# 612_jetracer_esp32s3_030100.net
KiCad netlist of a schematic drawn in EAGLE
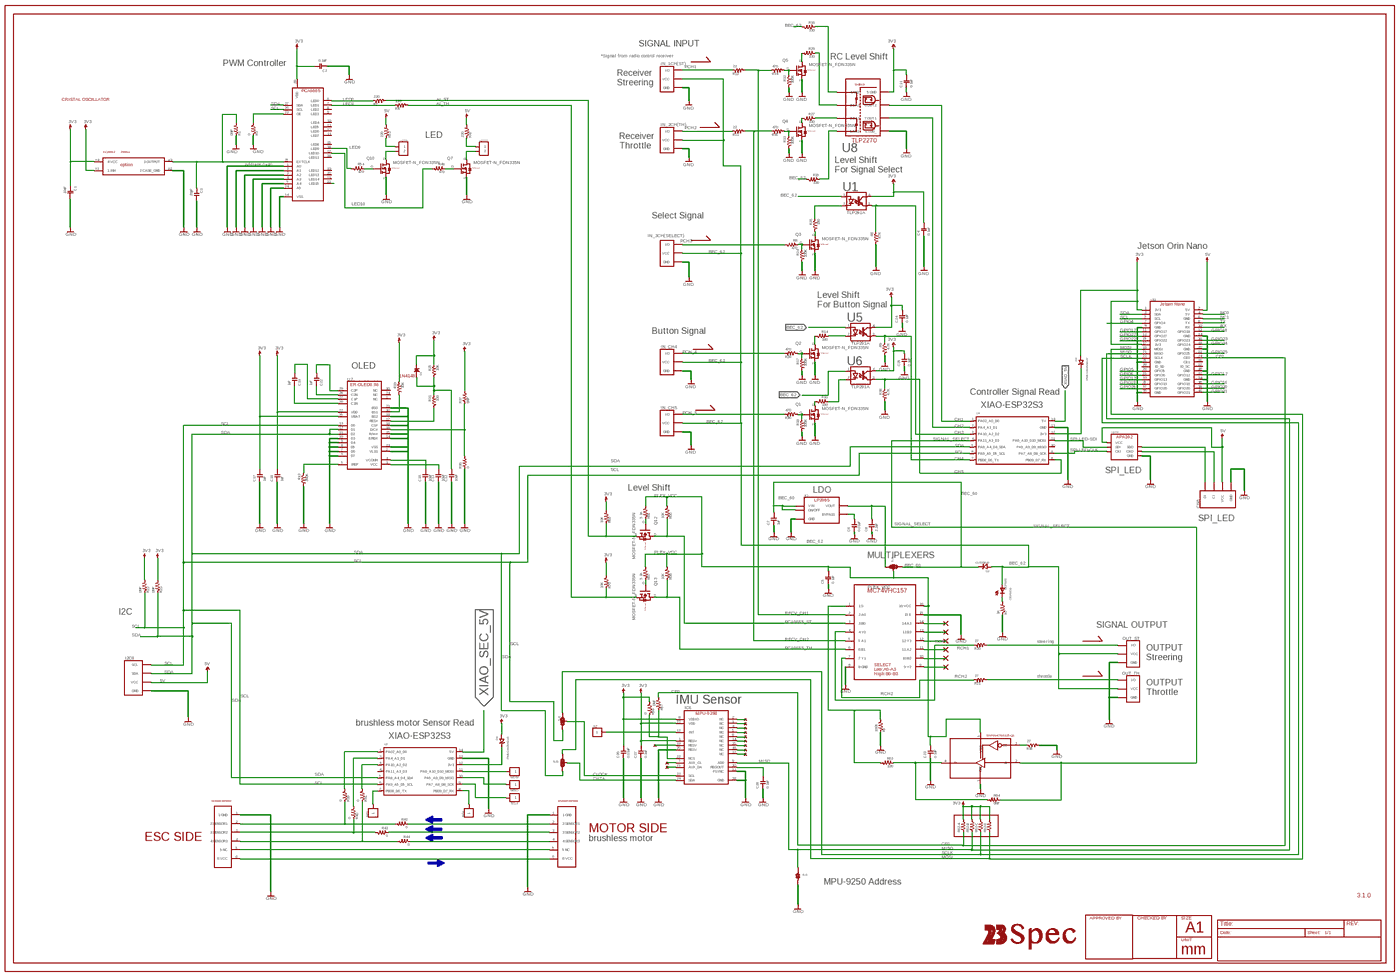
[diagram p0: schematic, sheet 1, overview]
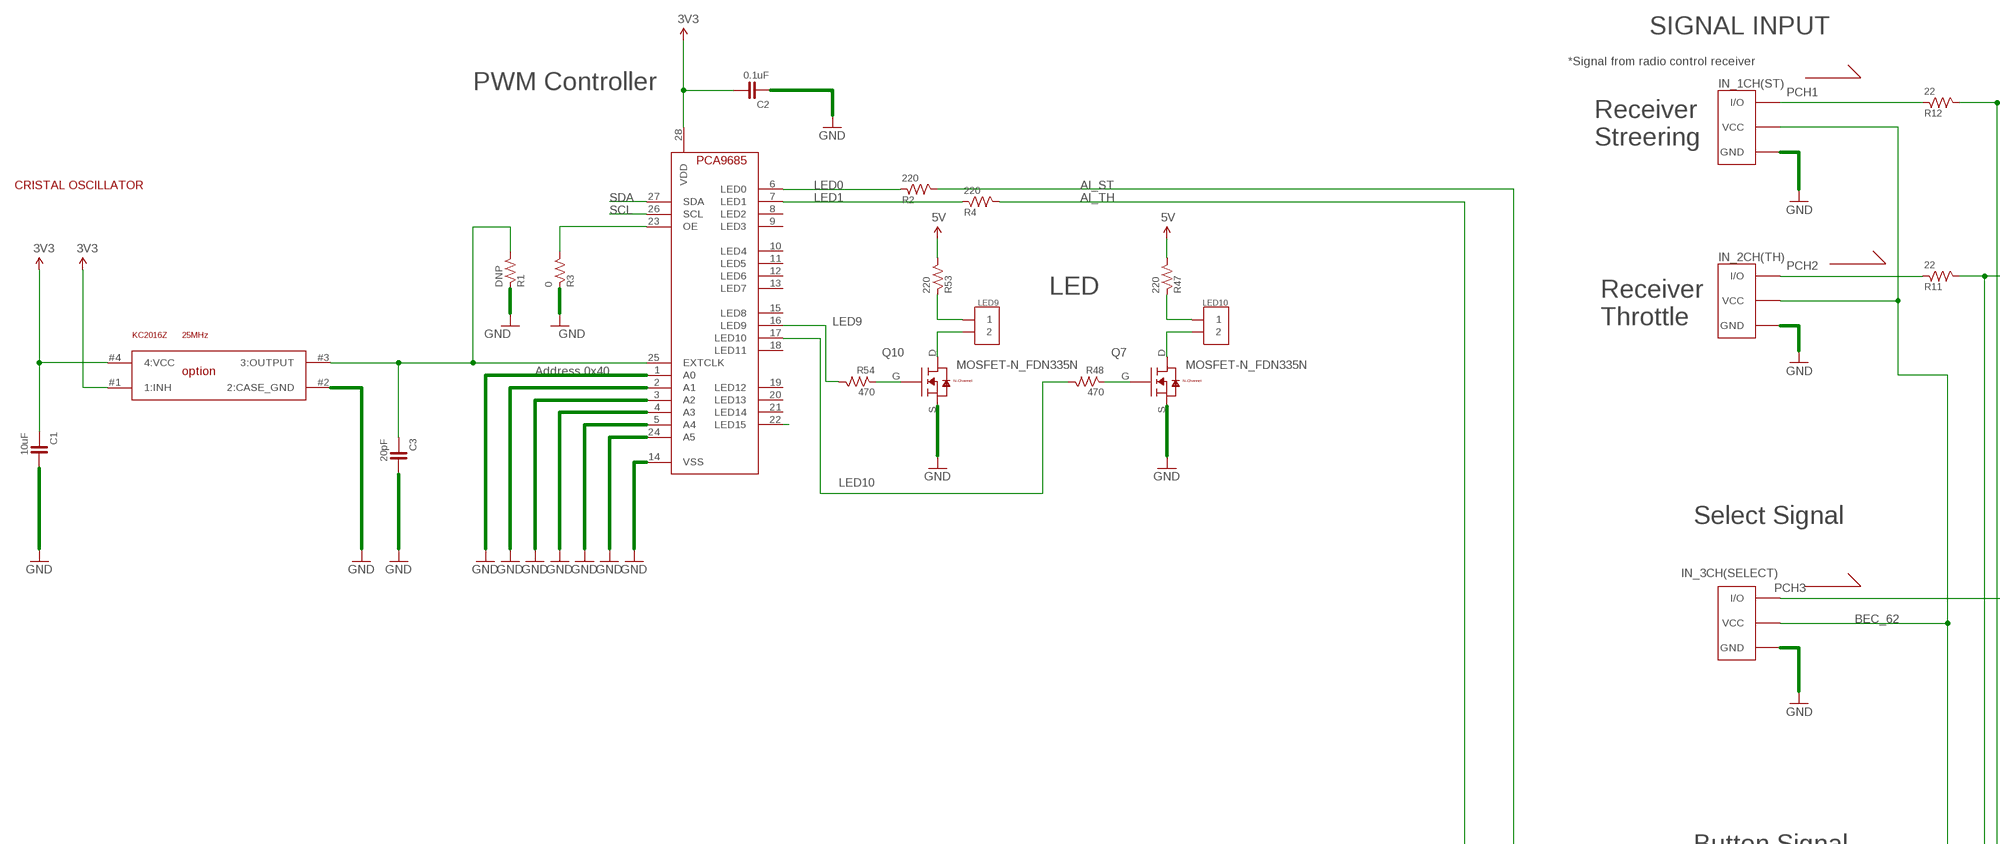
[diagram p1: schematic, sheet 1, part 1 of 4]
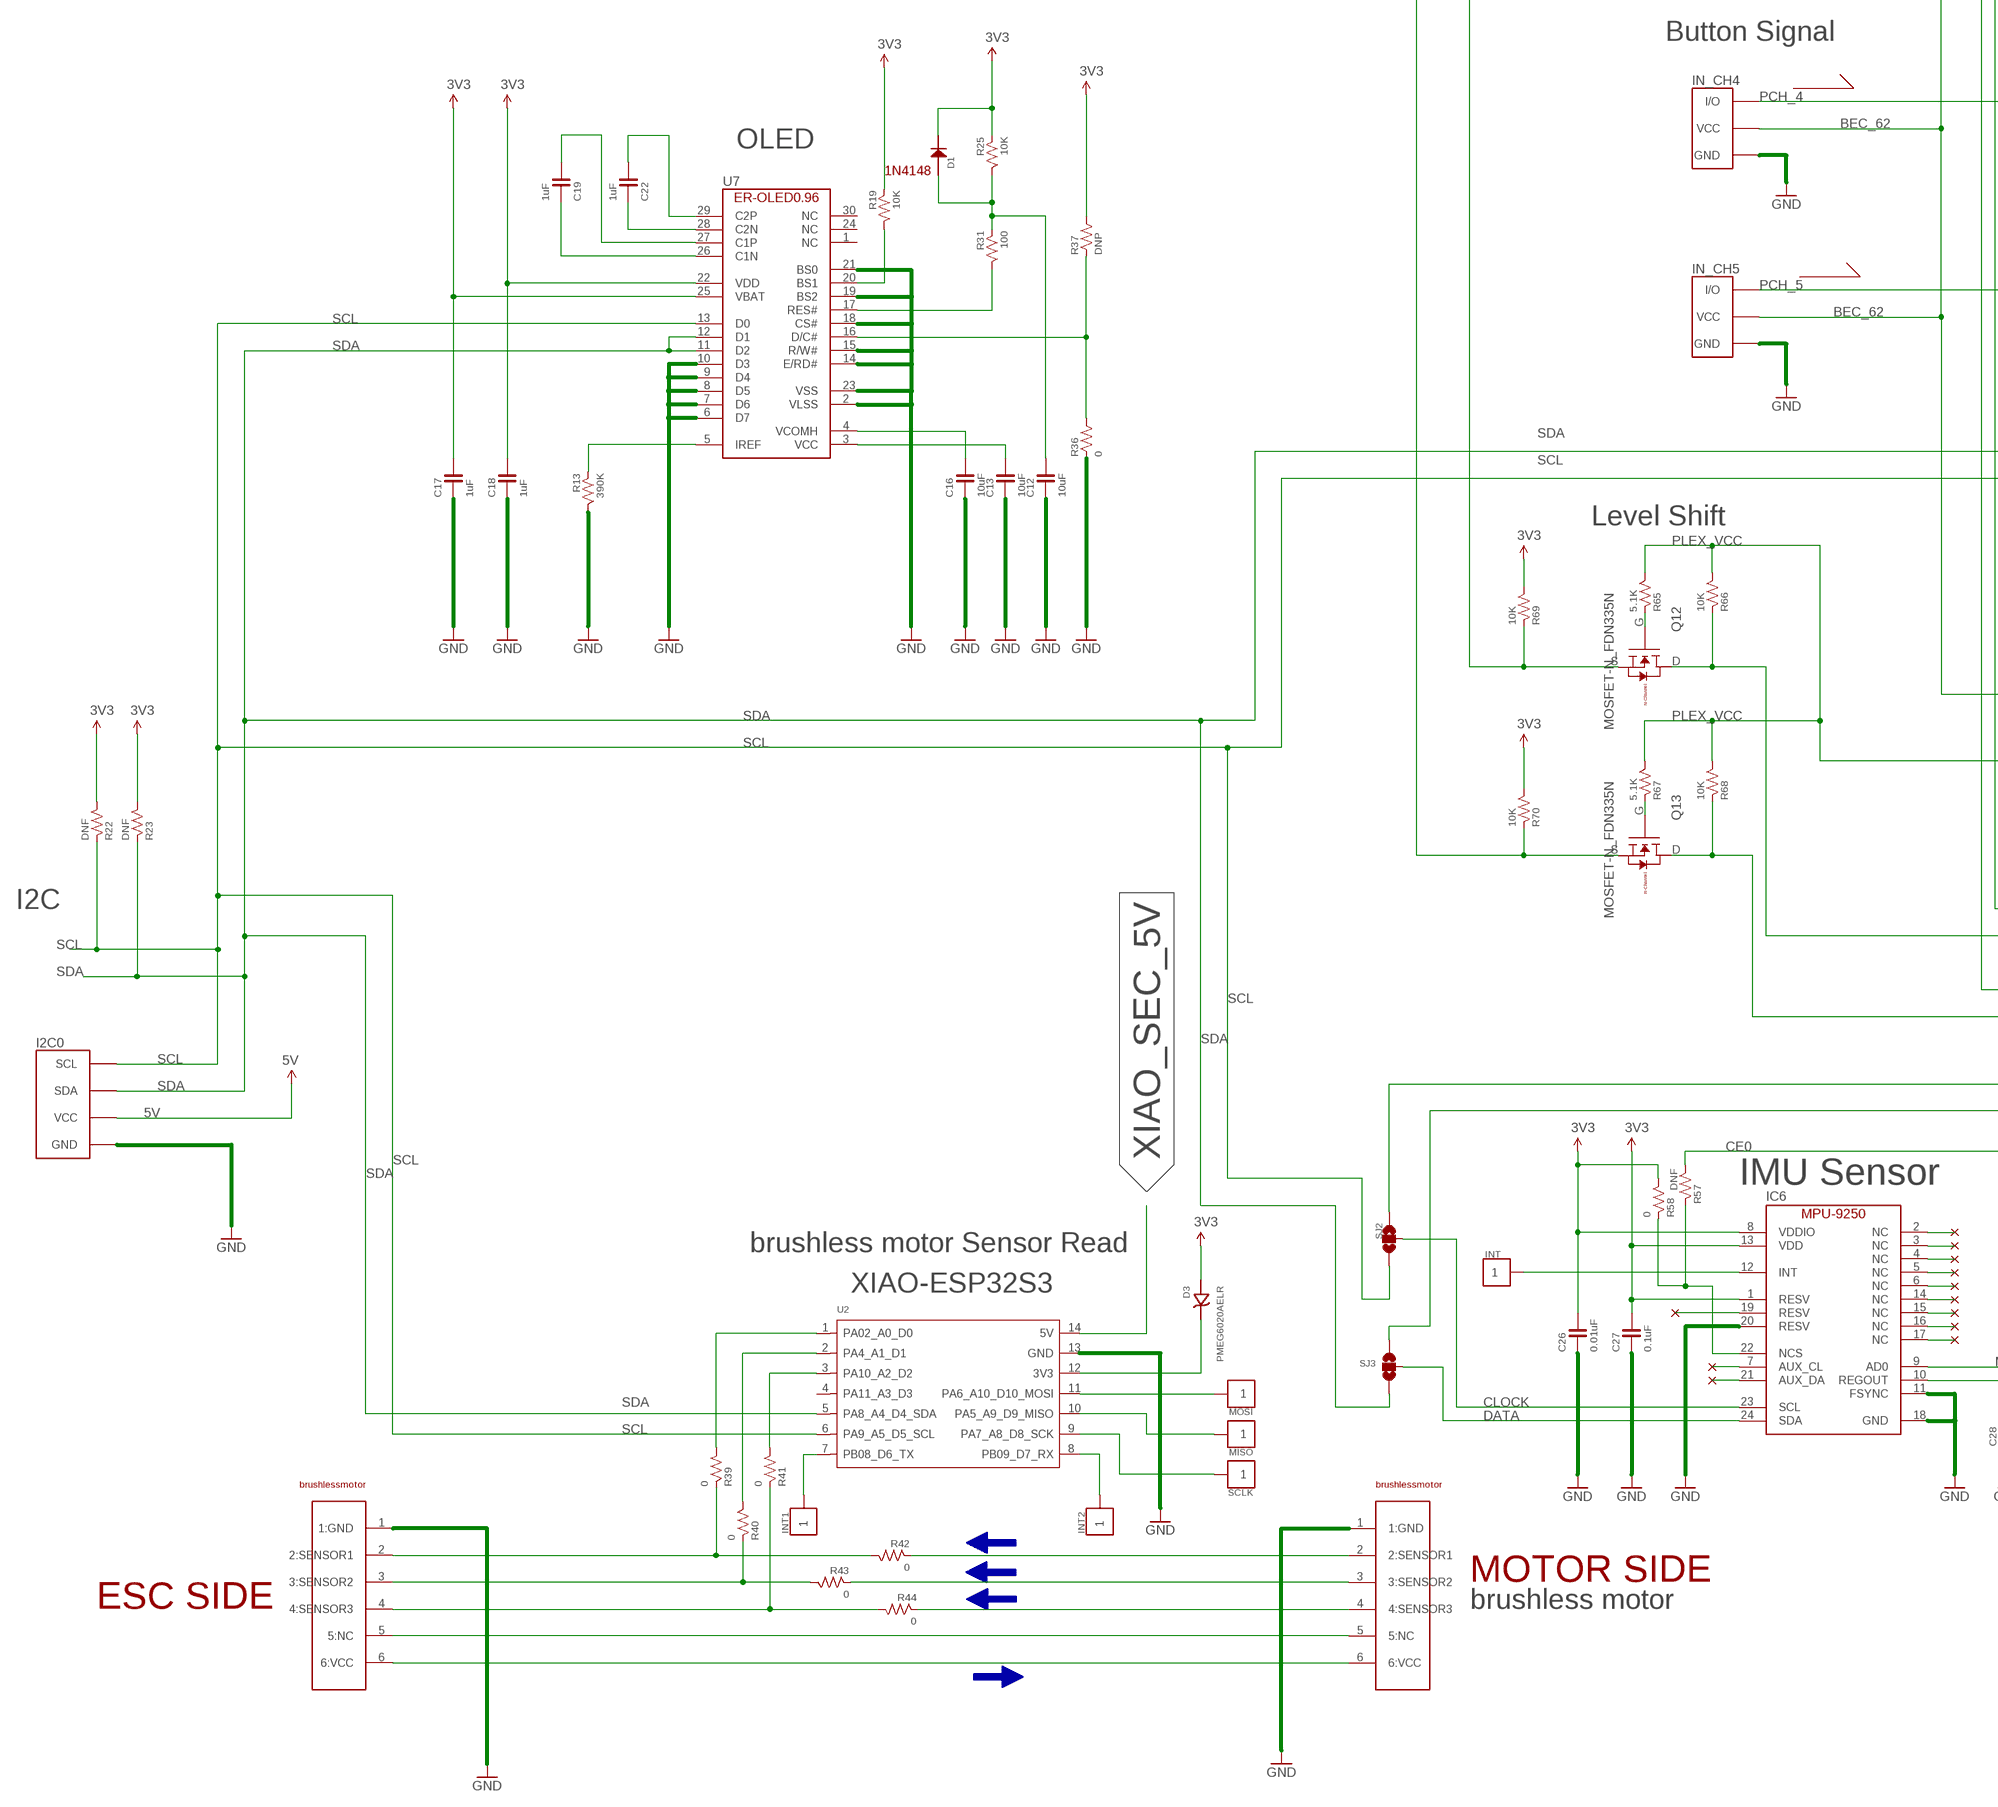
[diagram p2: schematic, sheet 1, part 2 of 4]
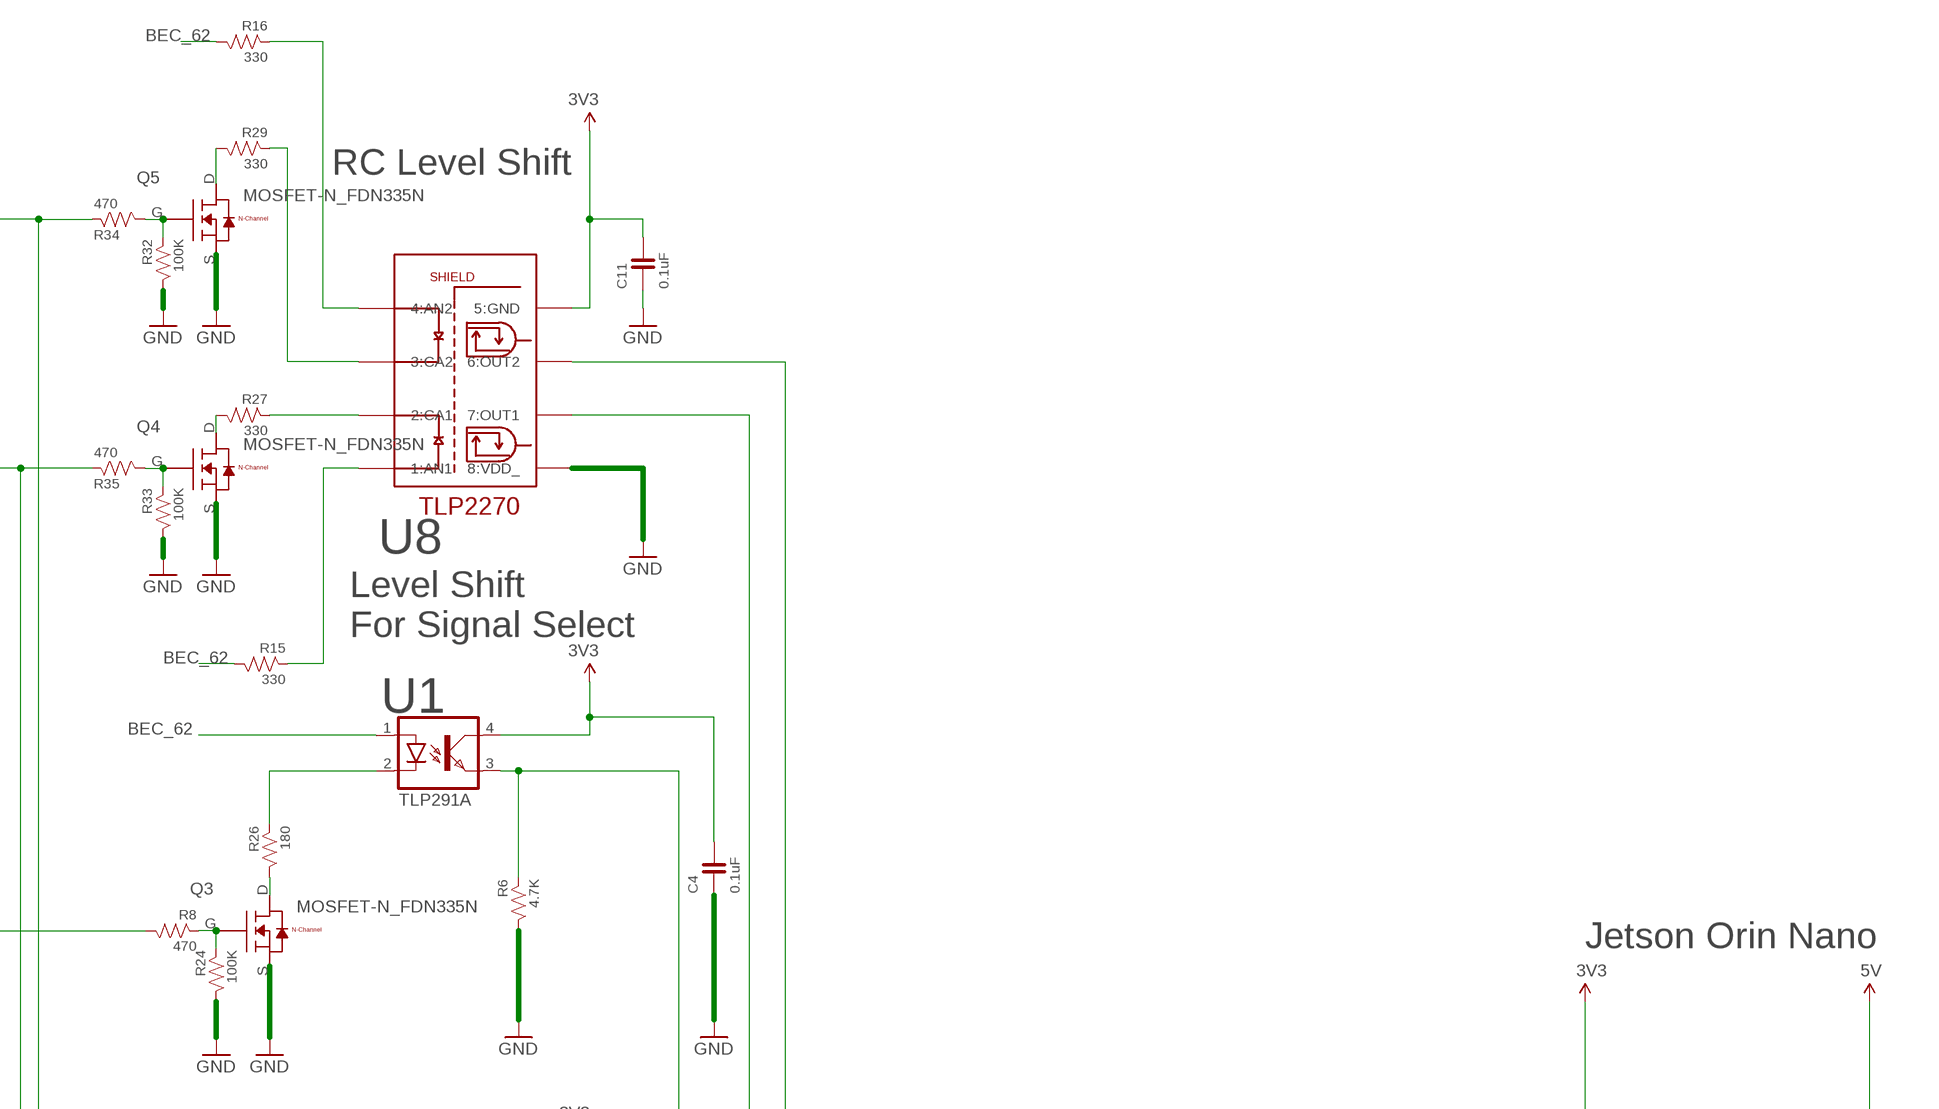
[diagram p3: schematic, sheet 1, part 3 of 4]
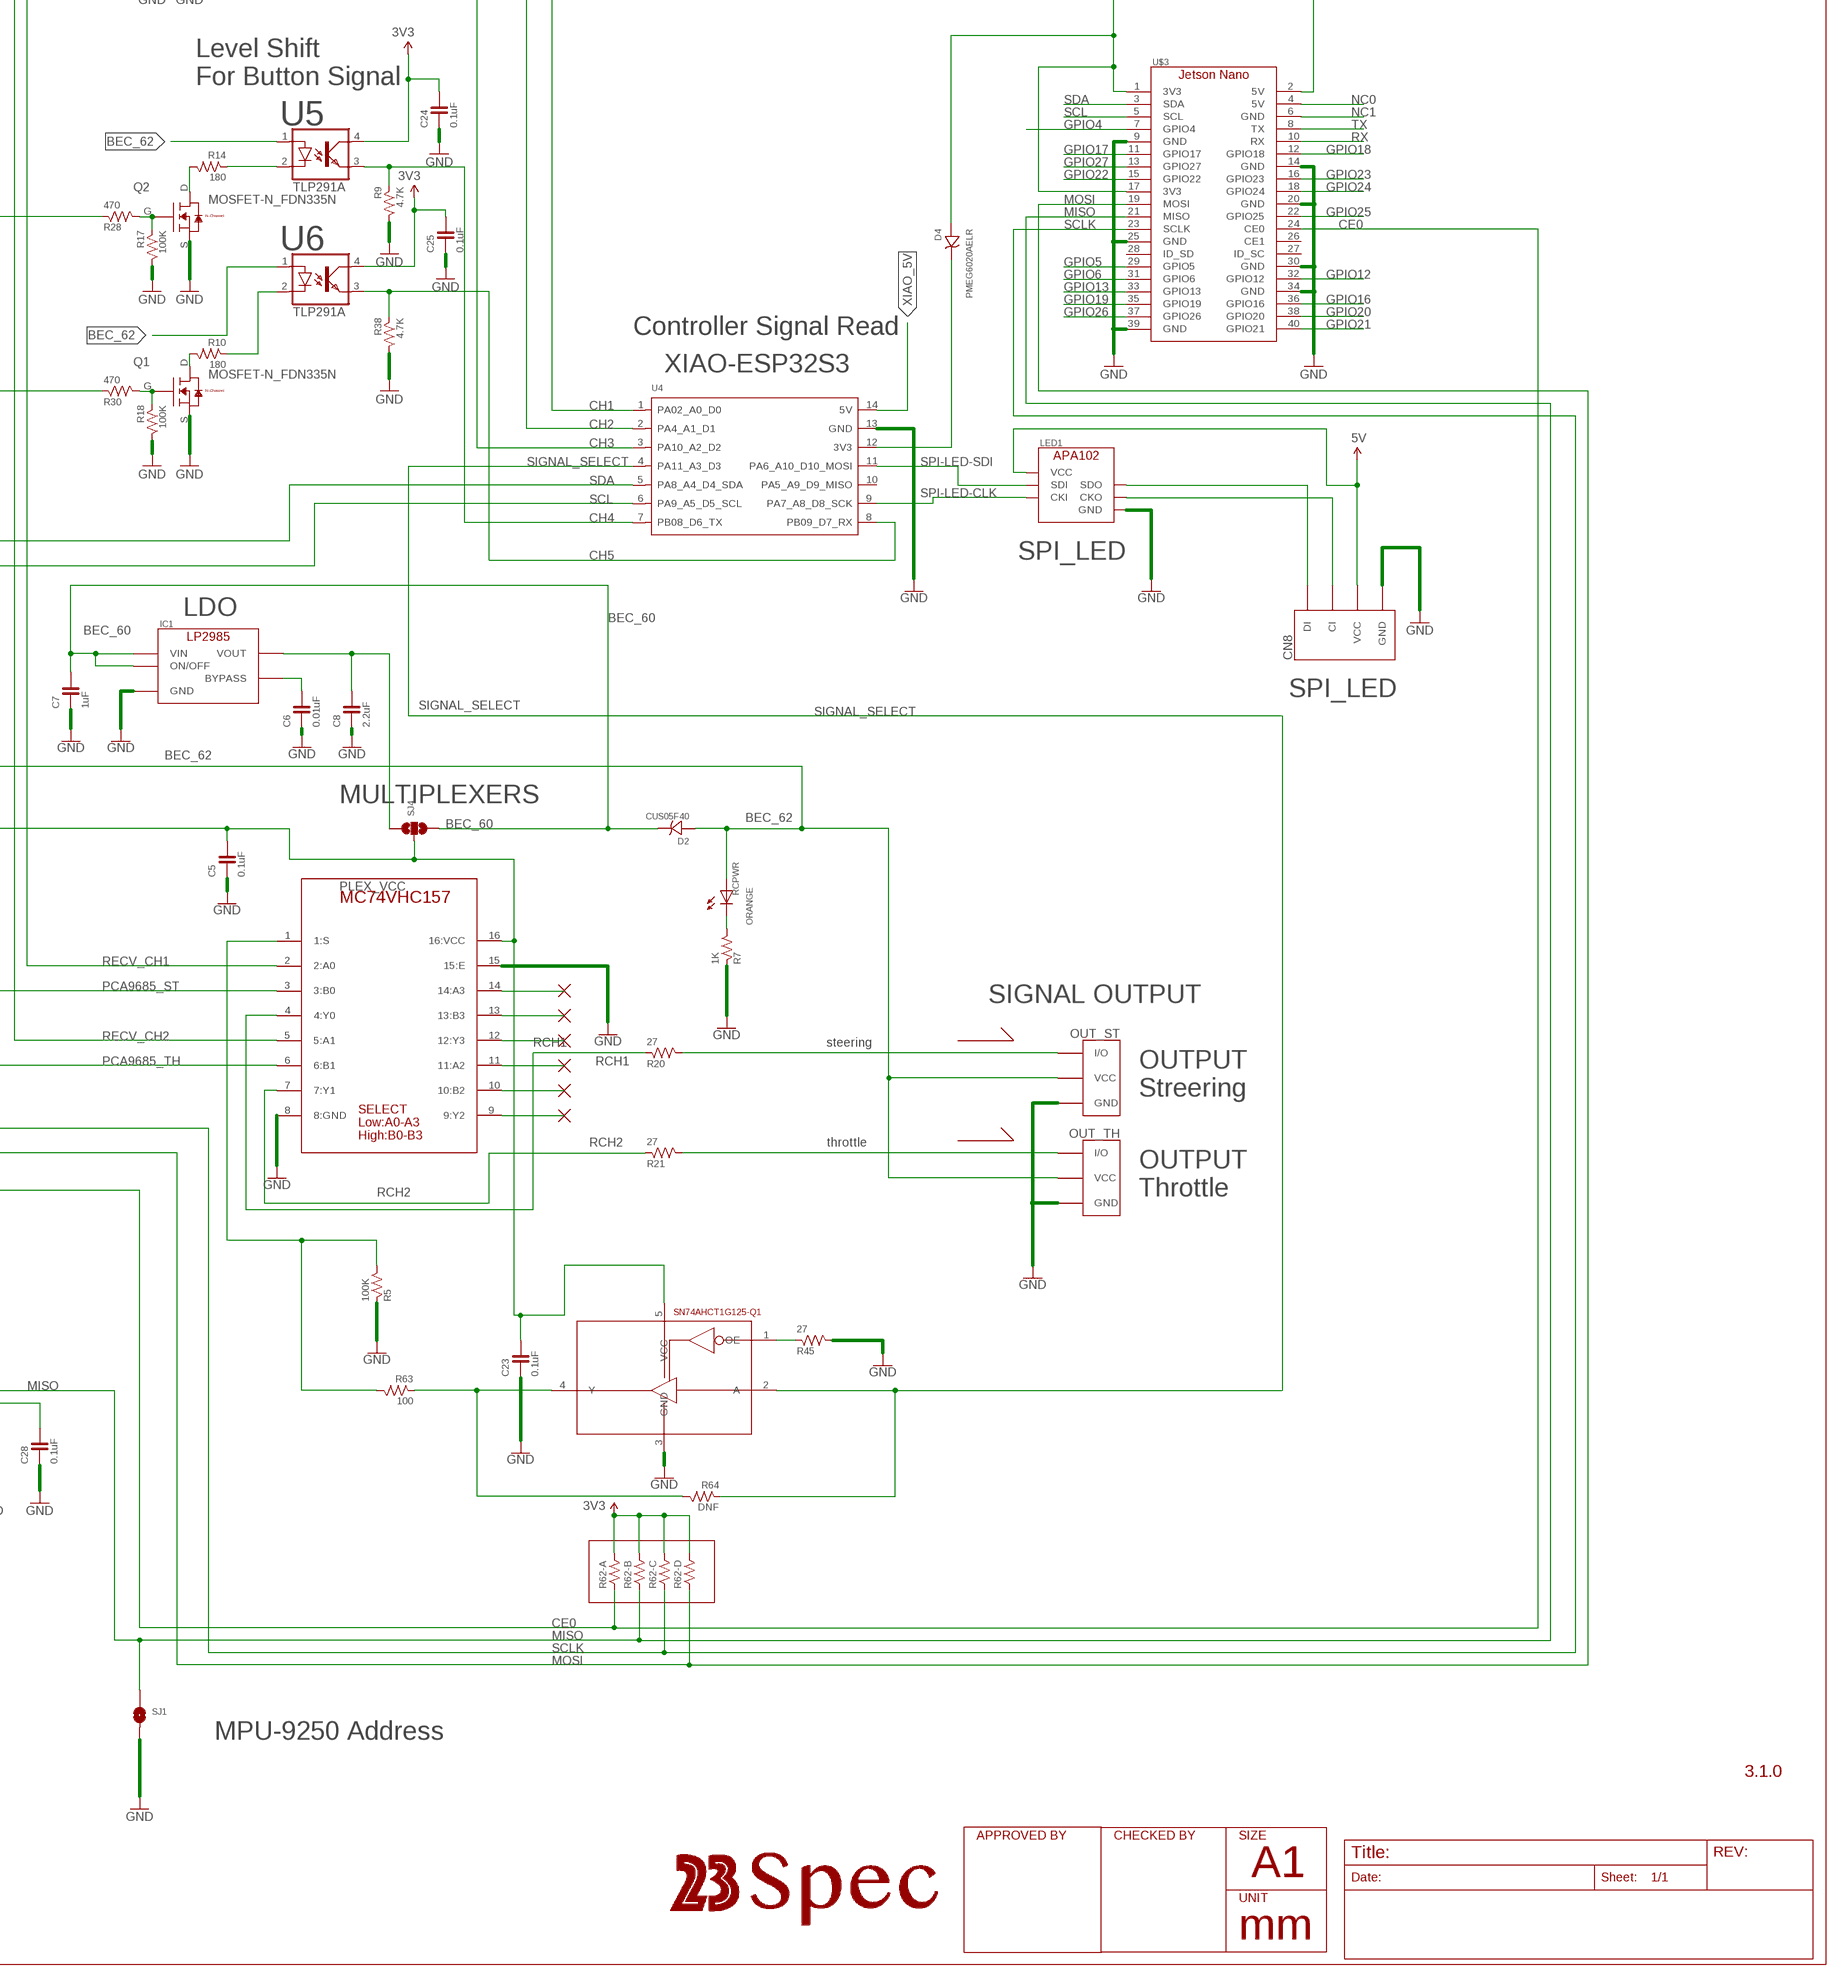
[diagram p4: schematic, sheet 1, part 4 of 4]

(export (version "E")
  (design (tool "Eeschema 10.0.6"))
  (components
    (comp (ref "C1")
      (value "10uF")
      (footprint "eagle-import:0603")
      (libsource (lib "eagle-import") (part "CAPACITOR-0603"))
    )
    (comp (ref "C2")
      (value "0.1uF")
      (footprint "eagle-import:0603")
      (libsource (lib "eagle-import") (part "CAPACITOR-0603"))
    )
    (comp (ref "C3")
      (value "20pF")
      (footprint "eagle-import:0603")
      (libsource (lib "eagle-import") (part "CAPACITOR-0603"))
    )
    (comp (ref "C4")
      (value "0.1uF")
      (footprint "eagle-import:0603")
      (libsource (lib "eagle-import") (part "CAPACITOR-0603"))
    )
    (comp (ref "C5")
      (value "0.1uF")
      (footprint "eagle-import:0603")
      (libsource (lib "eagle-import") (part "CAPACITOR-0603"))
    )
    (comp (ref "C6")
      (value "0.01uF")
      (footprint "eagle-import:0603")
      (libsource (lib "eagle-import") (part "CAPACITOR-0603"))
    )
    (comp (ref "C7")
      (value "1uF")
      (footprint "eagle-import:0603")
      (libsource (lib "eagle-import") (part "CAPACITOR-0603"))
    )
    (comp (ref "C8")
      (value "2.2uF")
      (footprint "eagle-import:0603")
      (libsource (lib "eagle-import") (part "CAPACITOR-0603"))
    )
    (comp (ref "C11")
      (value "0.1uF")
      (footprint "eagle-import:0603")
      (libsource (lib "eagle-import") (part "CAPACITOR-0603"))
    )
    (comp (ref "C12")
      (value "10uF")
      (footprint "eagle-import:0603")
      (libsource (lib "eagle-import") (part "CAPACITOR-0603"))
    )
    (comp (ref "C13")
      (value "10uF")
      (footprint "eagle-import:0603")
      (libsource (lib "eagle-import") (part "CAPACITOR-0603"))
    )
    (comp (ref "C16")
      (value "10uF")
      (footprint "eagle-import:0603")
      (libsource (lib "eagle-import") (part "CAPACITOR-0603"))
    )
    (comp (ref "C17")
      (value "1uF")
      (footprint "eagle-import:0603")
      (libsource (lib "eagle-import") (part "CAPACITOR-0603"))
    )
    (comp (ref "C18")
      (value "1uF")
      (footprint "eagle-import:0603")
      (libsource (lib "eagle-import") (part "CAPACITOR-0603"))
    )
    (comp (ref "C19")
      (value "1uF")
      (footprint "eagle-import:0603")
      (libsource (lib "eagle-import") (part "CAPACITOR-0603"))
    )
    (comp (ref "C22")
      (value "1uF")
      (footprint "eagle-import:0603")
      (libsource (lib "eagle-import") (part "CAPACITOR-0603"))
    )
    (comp (ref "C23")
      (value "0.1uF")
      (footprint "eagle-import:0603")
      (libsource (lib "eagle-import") (part "CAPACITOR-0603"))
    )
    (comp (ref "C24")
      (value "0.1uF")
      (footprint "eagle-import:0603")
      (libsource (lib "eagle-import") (part "CAPACITOR-0603"))
    )
    (comp (ref "C25")
      (value "0.1uF")
      (footprint "eagle-import:0603")
      (libsource (lib "eagle-import") (part "CAPACITOR-0603"))
    )
    (comp (ref "C26")
      (value "0.01uF")
      (footprint "eagle-import:0603")
      (libsource (lib "eagle-import") (part "CAPACITOR-0603"))
    )
    (comp (ref "C27")
      (value "0.1uF")
      (footprint "eagle-import:0603")
      (libsource (lib "eagle-import") (part "CAPACITOR-0603"))
    )
    (comp (ref "C28")
      (value "0.1uF")
      (footprint "eagle-import:0603")
      (libsource (lib "eagle-import") (part "CAPACITOR-0603"))
    )
    (comp (ref "CN8")
      (value "FABO-SPI-LED-B04B")
      (footprint "eagle-import:SPI-B04B-PASK-1")
      (libsource (lib "eagle-import") (part "FABO-SPI-LED-B04B"))
    )
    (comp (ref "D1")
      (value "1N4148")
      (footprint "eagle-import:1N4148W")
      (libsource (lib "eagle-import") (part "1N4148"))
    )
    (comp (ref "D2")
      (value "CUS05F40")
      (footprint "eagle-import:CUS05F40")
      (libsource (lib "eagle-import") (part "CUS05F40"))
    )
    (comp (ref "D3")
      (value "PMEG6020AELR")
      (footprint "eagle-import:SOD123W")
      (libsource (lib "eagle-import") (part "PMEG6020AELR"))
    )
    (comp (ref "D4")
      (value "PMEG6020AELR")
      (footprint "eagle-import:SOD123W")
      (libsource (lib "eagle-import") (part "PMEG6020AELR"))
    )
    (comp (ref "I2C0")
      (value "FABO_BRICK_I2C-B04B-PASK-1")
      (footprint "eagle-import:FABO_BRICK_I2C_B04B-PASK-1")
      (libsource (lib "eagle-import") (part "FABO_BRICK_I2C-B04B-PASK-1"))
    )
    (comp (ref "IC1")
      (value "LP2985-33DBV")
      (footprint "eagle-import:SOT-23-5")
      (libsource (lib "eagle-import") (part "LP2985-33DBV"))
    )
    (comp (ref "IC4")
      (value "PCA9685_BOTTOM")
      (footprint "eagle-import:PCA9685_BOTTOM")
      (libsource (lib "eagle-import") (part "PCA9685_BOTTOM"))
    )
    (comp (ref "IC6")
      (value "IS-MPU9250")
      (footprint "eagle-import:INVENSENSE-MPU9250")
      (libsource (lib "eagle-import") (part "IS-MPU9250"))
    )
    (comp (ref "INT")
      (value "PIN_1X1")
      (footprint "eagle-import:PIN_1X1")
      (libsource (lib "eagle-import") (part "PIN_1X1"))
    )
    (comp (ref "INT1")
      (value "PIN_1X1")
      (footprint "eagle-import:PIN_1X1")
      (libsource (lib "eagle-import") (part "PIN_1X1"))
    )
    (comp (ref "INT2")
      (value "PIN_1X1")
      (footprint "eagle-import:PIN_1X1")
      (libsource (lib "eagle-import") (part "PIN_1X1"))
    )
    (comp (ref "IN_1CH(ST)")
      (value "FABO_BRICK_3PIN-HEADER")
      (footprint "eagle-import:FABO_BRICK_3PIN_HEADER")
      (libsource (lib "eagle-import") (part "FABO_BRICK_3PIN-HEADER"))
    )
    (comp (ref "IN_2CH(TH)")
      (value "FABO_BRICK_3PIN-HEADER")
      (footprint "eagle-import:FABO_BRICK_3PIN_HEADER")
      (libsource (lib "eagle-import") (part "FABO_BRICK_3PIN-HEADER"))
    )
    (comp (ref "IN_3CH(SELECT)")
      (value "FABO_BRICK_3PIN-HEADER")
      (footprint "eagle-import:FABO_BRICK_3PIN_HEADER")
      (libsource (lib "eagle-import") (part "FABO_BRICK_3PIN-HEADER"))
    )
    (comp (ref "IN_CH4")
      (value "FABO_BRICK_3PIN-HEADER")
      (footprint "eagle-import:FABO_BRICK_3PIN_HEADER")
      (libsource (lib "eagle-import") (part "FABO_BRICK_3PIN-HEADER"))
    )
    (comp (ref "IN_CH5")
      (value "FABO_BRICK_3PIN-HEADER")
      (footprint "eagle-import:FABO_BRICK_3PIN_HEADER")
      (libsource (lib "eagle-import") (part "FABO_BRICK_3PIN-HEADER"))
    )
    (comp (ref "LED1")
      (value "APA102_IPIXEL")
      (footprint "eagle-import:APA102_2020")
      (libsource (lib "eagle-import") (part "APA102_IPIXEL"))
    )
    (comp (ref "LED9")
      (value "PIN_1X2")
      (footprint "eagle-import:PIN_1X2")
      (libsource (lib "eagle-import") (part "PIN_1X2"))
    )
    (comp (ref "LED10")
      (value "PIN_1X2")
      (footprint "eagle-import:PIN_1X2")
      (libsource (lib "eagle-import") (part "PIN_1X2"))
    )
    (comp (ref "MISO")
      (value "PIN_1X1")
      (footprint "eagle-import:PIN_1X1")
      (libsource (lib "eagle-import") (part "PIN_1X1"))
    )
    (comp (ref "MOSI")
      (value "PIN_1X1")
      (footprint "eagle-import:PIN_1X1")
      (libsource (lib "eagle-import") (part "PIN_1X1"))
    )
    (comp (ref "OUT_ST")
      (value "FABO_BRICK_3PIN-HEADER")
      (footprint "eagle-import:FABO_BRICK_3PIN_HEADER")
      (libsource (lib "eagle-import") (part "FABO_BRICK_3PIN-HEADER"))
    )
    (comp (ref "OUT_TH")
      (value "FABO_BRICK_3PIN-HEADER")
      (footprint "eagle-import:FABO_BRICK_3PIN_HEADER")
      (libsource (lib "eagle-import") (part "FABO_BRICK_3PIN-HEADER"))
    )
    (comp (ref "Q1")
      (value "MOSFET-N_FDN335N")
      (footprint "eagle-import:SUPERSOT-3")
      (libsource (lib "eagle-import") (part "MOSFET-N_FDN335N"))
    )
    (comp (ref "Q2")
      (value "MOSFET-N_FDN335N")
      (footprint "eagle-import:SUPERSOT-3")
      (libsource (lib "eagle-import") (part "MOSFET-N_FDN335N"))
    )
    (comp (ref "Q3")
      (value "MOSFET-N_FDN335N")
      (footprint "eagle-import:SUPERSOT-3")
      (libsource (lib "eagle-import") (part "MOSFET-N_FDN335N"))
    )
    (comp (ref "Q4")
      (value "MOSFET-N_FDN335N")
      (footprint "eagle-import:SUPERSOT-3")
      (libsource (lib "eagle-import") (part "MOSFET-N_FDN335N"))
    )
    (comp (ref "Q5")
      (value "MOSFET-N_FDN335N")
      (footprint "eagle-import:SUPERSOT-3")
      (libsource (lib "eagle-import") (part "MOSFET-N_FDN335N"))
    )
    (comp (ref "Q7")
      (value "MOSFET-N_FDN335N")
      (footprint "eagle-import:SUPERSOT-3")
      (libsource (lib "eagle-import") (part "MOSFET-N_FDN335N"))
    )
    (comp (ref "Q10")
      (value "MOSFET-N_FDN335N")
      (footprint "eagle-import:SUPERSOT-3")
      (libsource (lib "eagle-import") (part "MOSFET-N_FDN335N"))
    )
    (comp (ref "Q12")
      (value "MOSFET-N_FDN335N")
      (footprint "eagle-import:SUPERSOT-3")
      (libsource (lib "eagle-import") (part "MOSFET-N_FDN335N"))
    )
    (comp (ref "Q13")
      (value "MOSFET-N_FDN335N")
      (footprint "eagle-import:SUPERSOT-3")
      (libsource (lib "eagle-import") (part "MOSFET-N_FDN335N"))
    )
    (comp (ref "R1")
      (value "DNP")
      (footprint "eagle-import:0603")
      (libsource (lib "eagle-import") (part "RESISTOR-0603"))
    )
    (comp (ref "R2")
      (value "220")
      (footprint "eagle-import:0603")
      (libsource (lib "eagle-import") (part "RESISTOR-0603"))
    )
    (comp (ref "R3")
      (value "0")
      (footprint "eagle-import:0603")
      (libsource (lib "eagle-import") (part "RESISTOR-0603"))
    )
    (comp (ref "R4")
      (value "220")
      (footprint "eagle-import:0603")
      (libsource (lib "eagle-import") (part "RESISTOR-0603"))
    )
    (comp (ref "R5")
      (value "100K")
      (footprint "eagle-import:0603")
      (libsource (lib "eagle-import") (part "RESISTOR-0603"))
    )
    (comp (ref "R6")
      (value "4.7K")
      (footprint "eagle-import:0603")
      (libsource (lib "eagle-import") (part "RESISTOR-0603"))
    )
    (comp (ref "R7")
      (value "1K")
      (footprint "eagle-import:0603")
      (libsource (lib "eagle-import") (part "RESISTOR-0603"))
    )
    (comp (ref "R8")
      (value "470")
      (footprint "eagle-import:0603")
      (libsource (lib "eagle-import") (part "RESISTOR-0603"))
    )
    (comp (ref "R9")
      (value "4.7K")
      (footprint "eagle-import:0603")
      (libsource (lib "eagle-import") (part "RESISTOR-0603"))
    )
    (comp (ref "R10")
      (value "180")
      (footprint "eagle-import:0603")
      (libsource (lib "eagle-import") (part "RESISTOR-0603"))
    )
    (comp (ref "R11")
      (value "22")
      (footprint "eagle-import:0603")
      (libsource (lib "eagle-import") (part "RESISTOR-0603"))
    )
    (comp (ref "R12")
      (value "22")
      (footprint "eagle-import:0603")
      (libsource (lib "eagle-import") (part "RESISTOR-0603"))
    )
    (comp (ref "R13")
      (value "390K")
      (footprint "eagle-import:0603")
      (libsource (lib "eagle-import") (part "RESISTOR-0603"))
    )
    (comp (ref "R14")
      (value "180")
      (footprint "eagle-import:0603")
      (libsource (lib "eagle-import") (part "RESISTOR-0603"))
    )
    (comp (ref "R15")
      (value "330")
      (footprint "eagle-import:0603")
      (libsource (lib "eagle-import") (part "RESISTOR-0603"))
    )
    (comp (ref "R16")
      (value "330")
      (footprint "eagle-import:0603")
      (libsource (lib "eagle-import") (part "RESISTOR-0603"))
    )
    (comp (ref "R17")
      (value "100K")
      (footprint "eagle-import:0603")
      (libsource (lib "eagle-import") (part "RESISTOR-0603"))
    )
    (comp (ref "R18")
      (value "100K")
      (footprint "eagle-import:0603")
      (libsource (lib "eagle-import") (part "RESISTOR-0603"))
    )
    (comp (ref "R19")
      (value "10K")
      (footprint "eagle-import:0603")
      (libsource (lib "eagle-import") (part "RESISTOR-0603"))
    )
    (comp (ref "R20")
      (value "27")
      (footprint "eagle-import:0603")
      (libsource (lib "eagle-import") (part "RESISTOR-0603"))
    )
    (comp (ref "R21")
      (value "27")
      (footprint "eagle-import:0603")
      (libsource (lib "eagle-import") (part "RESISTOR-0603"))
    )
    (comp (ref "R22")
      (value "DNF")
      (footprint "eagle-import:0603")
      (libsource (lib "eagle-import") (part "RESISTOR-0603"))
    )
    (comp (ref "R23")
      (value "DNF")
      (footprint "eagle-import:0603")
      (libsource (lib "eagle-import") (part "RESISTOR-0603"))
    )
    (comp (ref "R24")
      (value "100K")
      (footprint "eagle-import:0603")
      (libsource (lib "eagle-import") (part "RESISTOR-0603"))
    )
    (comp (ref "R25")
      (value "10K")
      (footprint "eagle-import:0603")
      (libsource (lib "eagle-import") (part "RESISTOR-0603"))
    )
    (comp (ref "R26")
      (value "180")
      (footprint "eagle-import:0603")
      (libsource (lib "eagle-import") (part "RESISTOR-0603"))
    )
    (comp (ref "R27")
      (value "330")
      (footprint "eagle-import:0603")
      (libsource (lib "eagle-import") (part "RESISTOR-0603"))
    )
    (comp (ref "R28")
      (value "470")
      (footprint "eagle-import:0603")
      (libsource (lib "eagle-import") (part "RESISTOR-0603"))
    )
    (comp (ref "R29")
      (value "330")
      (footprint "eagle-import:0603")
      (libsource (lib "eagle-import") (part "RESISTOR-0603"))
    )
    (comp (ref "R30")
      (value "470")
      (footprint "eagle-import:0603")
      (libsource (lib "eagle-import") (part "RESISTOR-0603"))
    )
    (comp (ref "R31")
      (value "100")
      (footprint "eagle-import:0603")
      (libsource (lib "eagle-import") (part "RESISTOR-0603"))
    )
    (comp (ref "R32")
      (value "100K")
      (footprint "eagle-import:0603")
      (libsource (lib "eagle-import") (part "RESISTOR-0603"))
    )
    (comp (ref "R33")
      (value "100K")
      (footprint "eagle-import:0603")
      (libsource (lib "eagle-import") (part "RESISTOR-0603"))
    )
    (comp (ref "R34")
      (value "470")
      (footprint "eagle-import:0603")
      (libsource (lib "eagle-import") (part "RESISTOR-0603"))
    )
    (comp (ref "R35")
      (value "470")
      (footprint "eagle-import:0603")
      (libsource (lib "eagle-import") (part "RESISTOR-0603"))
    )
    (comp (ref "R36")
      (value "0")
      (footprint "eagle-import:0805")
      (libsource (lib "eagle-import") (part "RESISTOR-0805"))
    )
    (comp (ref "R37")
      (value "DNP")
      (footprint "eagle-import:0805")
      (fields (field (name "SPICEPREFIX") "R"))
      (libsource (lib "eagle-import") (part "RESISTOR-0805"))
    )
    (comp (ref "R38")
      (value "4.7K")
      (footprint "eagle-import:0603")
      (libsource (lib "eagle-import") (part "RESISTOR-0603"))
    )
    (comp (ref "R39")
      (value "0")
      (footprint "eagle-import:0603")
      (libsource (lib "eagle-import") (part "RESISTOR-0603"))
    )
    (comp (ref "R40")
      (value "0")
      (footprint "eagle-import:0603")
      (libsource (lib "eagle-import") (part "RESISTOR-0603"))
    )
    (comp (ref "R41")
      (value "0")
      (footprint "eagle-import:0603")
      (libsource (lib "eagle-import") (part "RESISTOR-0603"))
    )
    (comp (ref "R42")
      (value "0")
      (footprint "eagle-import:0603")
      (libsource (lib "eagle-import") (part "RESISTOR-0603"))
    )
    (comp (ref "R43")
      (value "0")
      (footprint "eagle-import:0603")
      (libsource (lib "eagle-import") (part "RESISTOR-0603"))
    )
    (comp (ref "R44")
      (value "0")
      (footprint "eagle-import:0603")
      (libsource (lib "eagle-import") (part "RESISTOR-0603"))
    )
    (comp (ref "R45")
      (value "27")
      (footprint "eagle-import:0603")
      (libsource (lib "eagle-import") (part "RESISTOR-0603"))
    )
    (comp (ref "R47")
      (value "220")
      (footprint "eagle-import:0603")
      (libsource (lib "eagle-import") (part "RESISTOR-0603"))
    )
    (comp (ref "R48")
      (value "470")
      (footprint "eagle-import:0603")
      (libsource (lib "eagle-import") (part "RESISTOR-0603"))
    )
    (comp (ref "R53")
      (value "220")
      (footprint "eagle-import:0603")
      (libsource (lib "eagle-import") (part "RESISTOR-0603"))
    )
    (comp (ref "R54")
      (value "470")
      (footprint "eagle-import:0603")
      (libsource (lib "eagle-import") (part "RESISTOR-0603"))
    )
    (comp (ref "R57")
      (value "DNF")
      (footprint "eagle-import:0603")
      (libsource (lib "eagle-import") (part "RESISTOR-0603"))
    )
    (comp (ref "R58")
      (value "0")
      (footprint "eagle-import:0603")
      (libsource (lib "eagle-import") (part "RESISTOR-0603"))
    )
    (comp (ref "R62")
      (value "RESISTOR_ARRAY_4")
      (footprint "eagle-import:EXBV8V")
      (libsource (lib "eagle-import") (part "RESISTOR_ARRAY_4"))
    )
    (comp (ref "R63")
      (value "100")
      (footprint "eagle-import:0603")
      (libsource (lib "eagle-import") (part "RESISTOR-0603"))
    )
    (comp (ref "R64")
      (value "DNF")
      (footprint "eagle-import:0603")
      (libsource (lib "eagle-import") (part "RESISTOR-0603"))
    )
    (comp (ref "R65")
      (value "5.1K")
      (footprint "eagle-import:0603")
      (libsource (lib "eagle-import") (part "RESISTOR-0603"))
    )
    (comp (ref "R66")
      (value "10K")
      (footprint "eagle-import:0603")
      (libsource (lib "eagle-import") (part "RESISTOR-0603"))
    )
    (comp (ref "R67")
      (value "5.1K")
      (footprint "eagle-import:0603")
      (libsource (lib "eagle-import") (part "RESISTOR-0603"))
    )
    (comp (ref "R68")
      (value "10K")
      (footprint "eagle-import:0603")
      (libsource (lib "eagle-import") (part "RESISTOR-0603"))
    )
    (comp (ref "R69")
      (value "10K")
      (footprint "eagle-import:0603")
      (libsource (lib "eagle-import") (part "RESISTOR-0603"))
    )
    (comp (ref "R70")
      (value "10K")
      (footprint "eagle-import:0603")
      (libsource (lib "eagle-import") (part "RESISTOR-0603"))
    )
    (comp (ref "RCPWR")
      (value "ORANGE")
      (footprint "eagle-import:0603")
      (libsource (lib "eagle-import") (part "LED-0603"))
    )
    (comp (ref "SCLK")
      (value "PIN_1X1")
      (footprint "eagle-import:PIN_1X1")
      (libsource (lib "eagle-import") (part "PIN_1X1"))
    )
    (comp (ref "SJ1")
      (value "FABO-SMD-JUMPER-SELECT")
      (footprint "eagle-import:SMD-JUMPER_SELECT")
      (libsource (lib "eagle-import") (part "FABO-SMD-JUMPER-SELECT"))
    )
    (comp (ref "SJ2")
      (value "SMD-JUMPER-3_23SHORT")
      (footprint "eagle-import:SMD-JUMPER-3-23SHORT")
      (libsource (lib "eagle-import") (part "SMD-JUMPER-3_23SHORT"))
    )
    (comp (ref "SJ3")
      (value "SMD-JUMPER-3_23SHORT")
      (footprint "eagle-import:SMD-JUMPER-3-23SHORT")
      (libsource (lib "eagle-import") (part "SMD-JUMPER-3_23SHORT"))
    )
    (comp (ref "SJ4")
      (value "SMD-JUMPER-3_23SHORT")
      (footprint "eagle-import:SMD-JUMPER-3-23SHORT")
      (libsource (lib "eagle-import") (part "SMD-JUMPER-3_23SHORT"))
    )
    (comp (ref "U$1")
      (value "MC74VHC157")
      (footprint "eagle-import:MC74VHC157_TSSOP-16")
      (libsource (lib "eagle-import") (part "MC74VHC157"))
    )
    (comp (ref "U$3")
      (value "JETSON_NANOJETSON_ORIN_NANO")
      (footprint "eagle-import:JETSON_ORIN_NANO_DIMENTION")
      (libsource (lib "eagle-import") (part "JETSON_NANOJETSON_ORIN_NANO"))
    )
    (comp (ref "U$8")
      (value "SN74AHCT1G125-Q1")
      (footprint "eagle-import:SC70")
      (libsource (lib "eagle-import") (part "SN74AHCT1G125-Q1"))
    )
    (comp (ref "U$9")
      (value "BRUSHLESSMOTOR_CON")
      (footprint "eagle-import:B6B-ZR")
      (libsource (lib "eagle-import") (part "BRUSHLESSMOTOR_CON"))
    )
    (comp (ref "U$10")
      (value "BRUSHLESSMOTOR_CON")
      (footprint "eagle-import:B6B-ZR")
      (libsource (lib "eagle-import") (part "BRUSHLESSMOTOR_CON"))
    )
    (comp (ref "U$11")
      (value "KC2016Z")
      (footprint "eagle-import:KC2016Z")
      (libsource (lib "eagle-import") (part "KC2016Z"))
    )
    (comp (ref "U1")
      (value "TLP291A")
      (footprint "eagle-import:11-3C1")
      (libsource (lib "eagle-import") (part "TLP291A"))
    )
    (comp (ref "U2")
      (value "MOUDLE-SEEEDUINO-XIAO-ESP32S3-SMD")
      (footprint "eagle-import:MOUDLE14P-SMD-2.54-21X17.8MM")
      (libsource (lib "eagle-import") (part "MOUDLE-SEEEDUINO-XIAO-ESP32S3-SMD"))
    )
    (comp (ref "U4")
      (value "MOUDLE-SEEEDUINO-XIAO-ESP32S3-SMD")
      (footprint "eagle-import:MOUDLE14P-SMD-2.54-21X17.8MM")
      (libsource (lib "eagle-import") (part "MOUDLE-SEEEDUINO-XIAO-ESP32S3-SMD"))
    )
    (comp (ref "U5")
      (value "TLP291A")
      (footprint "eagle-import:11-3C1")
      (libsource (lib "eagle-import") (part "TLP291A"))
    )
    (comp (ref "U6")
      (value "TLP291A")
      (footprint "eagle-import:11-3C1")
      (libsource (lib "eagle-import") (part "TLP291A"))
    )
    (comp (ref "U7")
      (value "ER-OLED0.96-1ER-CON30HT-1")
      (footprint "eagle-import:ER-CON30HT-1")
      (libsource (lib "eagle-import") (part "ER-OLED0.96-1ER-CON30HT-1"))
    )
    (comp (ref "U8")
      (value "TLP2270")
      (footprint "eagle-import:TLP2270")
      (libsource (lib "eagle-import") (part "TLP2270"))
    )
  )
  (nets
    (net (code "1") (name "/AI_ST") (class "Default")
      (node (ref "Q12") (pin "S") (pinfunction "S_S") (pintype "passive"))
      (node (ref "R2") (pin "2") (pinfunction "2_2") (pintype "bidirectional"))
      (node (ref "R69") (pin "1") (pinfunction "1_1") (pintype "bidirectional"))
    )
    (net (code "2") (name "/AI_TH") (class "Default")
      (node (ref "Q13") (pin "S") (pinfunction "S_S") (pintype "passive"))
      (node (ref "R4") (pin "2") (pinfunction "2_2") (pintype "bidirectional"))
      (node (ref "R70") (pin "1") (pinfunction "1_1") (pintype "bidirectional"))
    )
    (net (code "3") (name "/BEC_60") (class "Default")
      (node (ref "C7") (pin "2") (pinfunction "2_2") (pintype "passive"))
      (node (ref "D2") (pin "C") (pinfunction "CATHODE_C") (pintype "bidirectional"))
      (node (ref "IC1") (pin "1") (pinfunction "VIN_1") (pintype "input"))
      (node (ref "IC1") (pin "3") (pinfunction "ON/OFF_3") (pintype "input"))
      (node (ref "SJ4") (pin "3") (pinfunction "3_3") (pintype "passive"))
    )
    (net (code "4") (name "/CE0") (class "Default")
      (node (ref "R57") (pin "2") (pinfunction "2_2") (pintype "bidirectional"))
      (node (ref "R62") (pin "1") (pinfunction "1_1") (pintype "bidirectional"))
      (node (ref "U$3") (pin "24") (pinfunction "CE0_24") (pintype "bidirectional"))
    )
    (net (code "5") (name "/CH1") (class "Default")
      (node (ref "U4") (pin "1") (pinfunction "PA02_A0_D0_1") (pintype "bidirectional"))
      (node (ref "U8") (pin "6") (pinfunction "6:OUT2_6") (pintype "bidirectional"))
    )
    (net (code "6") (name "/CH2") (class "Default")
      (node (ref "U4") (pin "2") (pinfunction "PA4_A1_D1_2") (pintype "bidirectional"))
      (node (ref "U8") (pin "7") (pinfunction "7:OUT1_7") (pintype "bidirectional"))
    )
    (net (code "7") (name "/CH3") (class "Default")
      (node (ref "R6") (pin "1") (pinfunction "1_1") (pintype "bidirectional"))
      (node (ref "U1") (pin "3") (pinfunction "EMI_3") (pintype "passive"))
      (node (ref "U4") (pin "3") (pinfunction "PA10_A2_D2_3") (pintype "bidirectional"))
    )
    (net (code "8") (name "/CH4") (class "Default")
      (node (ref "R9") (pin "1") (pinfunction "1_1") (pintype "bidirectional"))
      (node (ref "U4") (pin "7") (pinfunction "PB08_D6_TX_7") (pintype "bidirectional"))
      (node (ref "U5") (pin "3") (pinfunction "EMI_3") (pintype "passive"))
    )
    (net (code "9") (name "/CH5") (class "Default")
      (node (ref "R38") (pin "1") (pinfunction "1_1") (pintype "bidirectional"))
      (node (ref "U4") (pin "8") (pinfunction "PB09_D7_RX_8") (pintype "bidirectional"))
      (node (ref "U6") (pin "3") (pinfunction "EMI_3") (pintype "passive"))
    )
    (net (code "10") (name "/CLOCK") (class "Default")
      (node (ref "IC6") (pin "23") (pinfunction "SCL_23") (pintype "bidirectional"))
      (node (ref "SJ2") (pin "2") (pinfunction "2_2") (pintype "passive"))
    )
    (net (code "11") (name "/DATA") (class "Default")
      (node (ref "IC6") (pin "24") (pinfunction "SDA_24") (pintype "bidirectional"))
      (node (ref "SJ3") (pin "2") (pinfunction "2_2") (pintype "passive"))
    )
    (net (code "12") (name "/GPIO4") (class "Default")
      (node (ref "U$3") (pin "7") (pinfunction "GPIO4_7") (pintype "bidirectional"))
    )
    (net (code "13") (name "/GPIO5") (class "Default")
      (node (ref "U$3") (pin "29") (pinfunction "GPIO5_29") (pintype "bidirectional"))
    )
    (net (code "14") (name "/GPIO6") (class "Default")
      (node (ref "U$3") (pin "31") (pinfunction "GPIO6_31") (pintype "bidirectional"))
    )
    (net (code "15") (name "/GPIO12") (class "Default")
      (node (ref "U$3") (pin "32") (pinfunction "GPIO12_32") (pintype "bidirectional"))
    )
    (net (code "16") (name "/GPIO13") (class "Default")
      (node (ref "U$3") (pin "33") (pinfunction "GPIO13_33") (pintype "bidirectional"))
    )
    (net (code "17") (name "/GPIO16") (class "Default")
      (node (ref "U$3") (pin "36") (pinfunction "GPIO16_36") (pintype "bidirectional"))
    )
    (net (code "18") (name "/GPIO17") (class "Default")
      (node (ref "U$3") (pin "11") (pinfunction "GPIO17_11") (pintype "bidirectional"))
    )
    (net (code "19") (name "/GPIO18") (class "Default")
      (node (ref "U$3") (pin "12") (pinfunction "GPIO18_12") (pintype "bidirectional"))
    )
    (net (code "20") (name "/GPIO19") (class "Default")
      (node (ref "U$3") (pin "35") (pinfunction "GPIO19_35") (pintype "bidirectional"))
    )
    (net (code "21") (name "/GPIO20") (class "Default")
      (node (ref "U$3") (pin "38") (pinfunction "GPIO20_38") (pintype "bidirectional"))
    )
    (net (code "22") (name "/GPIO21") (class "Default")
      (node (ref "U$3") (pin "40") (pinfunction "GPIO21_40") (pintype "bidirectional"))
    )
    (net (code "23") (name "/GPIO22") (class "Default")
      (node (ref "U$3") (pin "15") (pinfunction "GPIO22_15") (pintype "bidirectional"))
    )
    (net (code "24") (name "/GPIO23") (class "Default")
      (node (ref "U$3") (pin "16") (pinfunction "GPIO23_16") (pintype "bidirectional"))
    )
    (net (code "25") (name "/GPIO24") (class "Default")
      (node (ref "U$3") (pin "18") (pinfunction "GPIO24_18") (pintype "bidirectional"))
    )
    (net (code "26") (name "/GPIO25") (class "Default")
      (node (ref "U$3") (pin "22") (pinfunction "GPIO25_22") (pintype "bidirectional"))
    )
    (net (code "27") (name "/GPIO26") (class "Default")
      (node (ref "U$3") (pin "37") (pinfunction "GPIO26_37") (pintype "bidirectional"))
    )
    (net (code "28") (name "/GPIO27") (class "Default")
      (node (ref "U$3") (pin "13") (pinfunction "GPIO27_13") (pintype "bidirectional"))
    )
    (net (code "29") (name "/LED0") (class "Default")
      (node (ref "IC4") (pin "6") (pinfunction "LED0_6") (pintype "bidirectional"))
      (node (ref "R2") (pin "1") (pinfunction "1_1") (pintype "bidirectional"))
    )
    (net (code "30") (name "/LED1") (class "Default")
      (node (ref "IC4") (pin "7") (pinfunction "LED1_7") (pintype "bidirectional"))
      (node (ref "R4") (pin "1") (pinfunction "1_1") (pintype "bidirectional"))
    )
    (net (code "31") (name "/LED9") (class "Default")
      (node (ref "IC4") (pin "16") (pinfunction "LED9_16") (pintype "bidirectional"))
      (node (ref "R54") (pin "2") (pinfunction "2_2") (pintype "bidirectional"))
    )
    (net (code "32") (name "/LED10") (class "Default")
      (node (ref "IC4") (pin "17") (pinfunction "LED10_17") (pintype "bidirectional"))
      (node (ref "R48") (pin "2") (pinfunction "2_2") (pintype "bidirectional"))
    )
    (net (code "33") (name "/MISO") (class "Default")
      (node (ref "IC6") (pin "9") (pinfunction "AD0_9") (pintype "bidirectional"))
      (node (ref "R62") (pin "2") (pinfunction "1_2") (pintype "bidirectional"))
      (node (ref "SJ1") (pin "1") (pinfunction "1_1") (pintype "passive"))
      (node (ref "U$3") (pin "21") (pinfunction "MISO_21") (pintype "bidirectional"))
    )
    (net (code "34") (name "/MOSI") (class "Default")
      (node (ref "R62") (pin "4") (pinfunction "1_4") (pintype "bidirectional"))
      (node (ref "SJ3") (pin "1") (pinfunction "1_1") (pintype "passive"))
      (node (ref "U$3") (pin "19") (pinfunction "MOSI_19") (pintype "bidirectional"))
    )
    (net (code "35") (name "/NC0") (class "Default")
      (node (ref "U$3") (pin "4") (pinfunction "5V_4") (pintype "bidirectional"))
    )
    (net (code "36") (name "/NC1") (class "Default")
      (node (ref "U$3") (pin "6") (pinfunction "GND_6") (pintype "bidirectional"))
    )
    (net (code "37") (name "/PCA9685_ST") (class "Default")
      (node (ref "Q12") (pin "D") (pinfunction "D_D") (pintype "passive"))
      (node (ref "R66") (pin "1") (pinfunction "1_1") (pintype "bidirectional"))
      (node (ref "U$1") (pin "3") (pinfunction "3:B0_3") (pintype "bidirectional"))
    )
    (net (code "38") (name "/PCA9685_TH") (class "Default")
      (node (ref "Q13") (pin "D") (pinfunction "D_D") (pintype "passive"))
      (node (ref "R68") (pin "1") (pinfunction "1_1") (pintype "bidirectional"))
      (node (ref "U$1") (pin "6") (pinfunction "6:B1_6") (pintype "bidirectional"))
    )
    (net (code "39") (name "/PCH1") (class "Default")
      (node (ref "IN_1CH(ST)") (pin "I/O") (pinfunction "I/O_I/O") (pintype "bidirectional"))
      (node (ref "R12") (pin "1") (pinfunction "1_1") (pintype "bidirectional"))
    )
    (net (code "40") (name "/PCH2") (class "Default")
      (node (ref "IN_2CH(TH)") (pin "I/O") (pinfunction "I/O_I/O") (pintype "bidirectional"))
      (node (ref "R11") (pin "1") (pinfunction "1_1") (pintype "bidirectional"))
    )
    (net (code "41") (name "/PCH3") (class "Default")
      (node (ref "IN_3CH(SELECT)") (pin "I/O") (pinfunction "I/O_I/O") (pintype "bidirectional"))
      (node (ref "R8") (pin "2") (pinfunction "2_2") (pintype "bidirectional"))
    )
    (net (code "42") (name "/PCH_4") (class "Default")
      (node (ref "IN_CH4") (pin "I/O") (pinfunction "I/O_I/O") (pintype "bidirectional"))
      (node (ref "R28") (pin "1") (pinfunction "1_1") (pintype "bidirectional"))
    )
    (net (code "43") (name "/PCH_5") (class "Default")
      (node (ref "IN_CH5") (pin "I/O") (pinfunction "I/O_I/O") (pintype "bidirectional"))
      (node (ref "R30") (pin "1") (pinfunction "1_1") (pintype "bidirectional"))
    )
    (net (code "44") (name "/PLEX_VCC") (class "Default")
      (node (ref "C23") (pin "2") (pinfunction "2_2") (pintype "passive"))
      (node (ref "C5") (pin "2") (pinfunction "2_2") (pintype "passive"))
      (node (ref "R65") (pin "2") (pinfunction "2_2") (pintype "bidirectional"))
      (node (ref "R66") (pin "2") (pinfunction "2_2") (pintype "bidirectional"))
      (node (ref "R67") (pin "2") (pinfunction "2_2") (pintype "bidirectional"))
      (node (ref "R68") (pin "2") (pinfunction "2_2") (pintype "bidirectional"))
      (node (ref "SJ4") (pin "2") (pinfunction "2_2") (pintype "passive"))
      (node (ref "U$1") (pin "16") (pinfunction "16:VCC_16") (pintype "bidirectional"))
      (node (ref "U$8") (pin "5") (pinfunction "VCC_5") (pintype "bidirectional"))
    )
    (net (code "45") (name "/RCH1") (class "Default")
      (node (ref "R20") (pin "1") (pinfunction "1_1") (pintype "bidirectional"))
      (node (ref "U$1") (pin "4") (pinfunction "4:Y0_4") (pintype "bidirectional"))
    )
    (net (code "46") (name "/RCH2") (class "Default")
      (node (ref "R21") (pin "1") (pinfunction "1_1") (pintype "bidirectional"))
      (node (ref "U$1") (pin "7") (pinfunction "7:Y1_7") (pintype "bidirectional"))
    )
    (net (code "47") (name "/RECV_CH1") (class "Default")
      (node (ref "R12") (pin "2") (pinfunction "2_2") (pintype "bidirectional"))
      (node (ref "R34") (pin "1") (pinfunction "1_1") (pintype "bidirectional"))
      (node (ref "U$1") (pin "2") (pinfunction "2:A0_2") (pintype "bidirectional"))
    )
    (net (code "48") (name "/RECV_CH2") (class "Default")
      (node (ref "R11") (pin "2") (pinfunction "2_2") (pintype "bidirectional"))
      (node (ref "R35") (pin "1") (pinfunction "1_1") (pintype "bidirectional"))
      (node (ref "U$1") (pin "5") (pinfunction "5:A1_5") (pintype "bidirectional"))
    )
    (net (code "49") (name "/RX") (class "Default")
      (node (ref "U$3") (pin "10") (pinfunction "RX_10") (pintype "bidirectional"))
    )
    (net (code "50") (name "/SCL") (class "Default")
      (node (ref "I2C0") (pin "SCL") (pinfunction "SCL_SCL") (pintype "bidirectional"))
      (node (ref "IC4") (pin "26") (pinfunction "SCL_26") (pintype "bidirectional"))
      (node (ref "R22") (pin "1") (pinfunction "1_1") (pintype "bidirectional"))
      (node (ref "SJ2") (pin "3") (pinfunction "3_3") (pintype "passive"))
      (node (ref "U$3") (pin "5") (pinfunction "SCL_5") (pintype "bidirectional"))
      (node (ref "U2") (pin "6") (pinfunction "PA9_A5_D5_SCL_6") (pintype "bidirectional"))
      (node (ref "U4") (pin "6") (pinfunction "PA9_A5_D5_SCL_6") (pintype "bidirectional"))
      (node (ref "U7") (pin "13") (pinfunction "D0_13") (pintype "bidirectional"))
    )
    (net (code "51") (name "/SCLK") (class "Default")
      (node (ref "R62") (pin "3") (pinfunction "1_3") (pintype "bidirectional"))
      (node (ref "SJ2") (pin "1") (pinfunction "1_1") (pintype "passive"))
      (node (ref "U$3") (pin "23") (pinfunction "SCLK_23") (pintype "bidirectional"))
    )
    (net (code "52") (name "/SDA") (class "Default")
      (node (ref "I2C0") (pin "SDA") (pinfunction "SDA_SDA") (pintype "bidirectional"))
      (node (ref "IC4") (pin "27") (pinfunction "SDA_27") (pintype "bidirectional"))
      (node (ref "R23") (pin "1") (pinfunction "1_1") (pintype "bidirectional"))
      (node (ref "SJ3") (pin "3") (pinfunction "3_3") (pintype "passive"))
      (node (ref "U$3") (pin "3") (pinfunction "SDA_3") (pintype "bidirectional"))
      (node (ref "U2") (pin "5") (pinfunction "PA8_A4_D4_SDA_5") (pintype "bidirectional"))
      (node (ref "U4") (pin "5") (pinfunction "PA8_A4_D4_SDA_5") (pintype "bidirectional"))
      (node (ref "U7") (pin "11") (pinfunction "D2_11") (pintype "bidirectional"))
      (node (ref "U7") (pin "12") (pinfunction "D1_12") (pintype "bidirectional"))
    )
    (net (code "53") (name "/SIGNAL_SELECT") (class "Default")
      (node (ref "R64") (pin "1") (pinfunction "1_1") (pintype "bidirectional"))
      (node (ref "U$8") (pin "2") (pinfunction "A_2") (pintype "bidirectional"))
      (node (ref "U4") (pin "4") (pinfunction "PA11_A3_D3_4") (pintype "bidirectional"))
    )
    (net (code "54") (name "/SPI-LED-CLK") (class "Default")
      (node (ref "LED1") (pin "CKI") (pinfunction "CKI_CKI") (pintype "bidirectional"))
      (node (ref "U4") (pin "9") (pinfunction "PA7_A8_D8_SCK_9") (pintype "bidirectional"))
    )
    (net (code "55") (name "/SPI-LED-SDI") (class "Default")
      (node (ref "LED1") (pin "SDI") (pinfunction "SDI_SDI") (pintype "bidirectional"))
      (node (ref "U4") (pin "11") (pinfunction "PA6_A10_D10_MOSI_11") (pintype "bidirectional"))
    )
    (net (code "56") (name "/TX") (class "Default")
      (node (ref "U$3") (pin "8") (pinfunction "TX_8") (pintype "bidirectional"))
    )
    (net (code "57") (name "3V3") (class "Default")
      (node (ref "C1") (pin "1") (pinfunction "1_1") (pintype "passive"))
      (node (ref "C11") (pin "2") (pinfunction "2_2") (pintype "passive"))
      (node (ref "C17") (pin "2") (pinfunction "2_2") (pintype "passive"))
      (node (ref "C18") (pin "2") (pinfunction "2_2") (pintype "passive"))
      (node (ref "C2") (pin "2") (pinfunction "2_2") (pintype "passive"))
      (node (ref "C24") (pin "2") (pinfunction "2_2") (pintype "passive"))
      (node (ref "C25") (pin "2") (pinfunction "2_2") (pintype "passive"))
      (node (ref "C26") (pin "2") (pinfunction "2_2") (pintype "passive"))
      (node (ref "C27") (pin "2") (pinfunction "2_2") (pintype "passive"))
      (node (ref "C4") (pin "2") (pinfunction "2_2") (pintype "passive"))
      (node (ref "D1") (pin "CATHODE") (pinfunction "CATHODE_CATHODE") (pintype "bidirectional"))
      (node (ref "D3") (pin "2") (pinfunction "ANODE_2") (pintype "bidirectional"))
      (node (ref "D4") (pin "2") (pinfunction "ANODE_2") (pintype "bidirectional"))
      (node (ref "IC4") (pin "28") (pinfunction "VDD_28") (pintype "bidirectional"))
      (node (ref "IC6") (pin "1") (pinfunction "RESV_1") (pintype "bidirectional"))
      (node (ref "IC6") (pin "13") (pinfunction "VDD_13") (pintype "bidirectional"))
      (node (ref "IC6") (pin "8") (pinfunction "VDDIO_8") (pintype "bidirectional"))
      (node (ref "R19") (pin "1") (pinfunction "1_1") (pintype "bidirectional"))
      (node (ref "R22") (pin "2") (pinfunction "2_2") (pintype "bidirectional"))
      (node (ref "R23") (pin "2") (pinfunction "2_2") (pintype "bidirectional"))
      (node (ref "R25") (pin "1") (pinfunction "1_1") (pintype "bidirectional"))
      (node (ref "R37") (pin "2") (pinfunction "2_2") (pintype "bidirectional"))
      (node (ref "R58") (pin "2") (pinfunction "2_2") (pintype "bidirectional"))
      (node (ref "R62") (pin "5") (pinfunction "2_5") (pintype "bidirectional"))
      (node (ref "R62") (pin "6") (pinfunction "2_6") (pintype "bidirectional"))
      (node (ref "R62") (pin "7") (pinfunction "2_7") (pintype "bidirectional"))
      (node (ref "R62") (pin "8") (pinfunction "2_8") (pintype "bidirectional"))
      (node (ref "R69") (pin "2") (pinfunction "2_2") (pintype "bidirectional"))
      (node (ref "R70") (pin "2") (pinfunction "2_2") (pintype "bidirectional"))
      (node (ref "U$11") (pin "#1") (pinfunction "1:INH_#1") (pintype "bidirectional"))
      (node (ref "U$11") (pin "#4") (pinfunction "4:VCC_#4") (pintype "bidirectional"))
      (node (ref "U$3") (pin "1") (pinfunction "3V3_1") (pintype "bidirectional"))
      (node (ref "U$3") (pin "17") (pinfunction "3V3_17") (pintype "bidirectional"))
      (node (ref "U1") (pin "4") (pinfunction "COL_4") (pintype "passive"))
      (node (ref "U5") (pin "4") (pinfunction "COL_4") (pintype "passive"))
      (node (ref "U6") (pin "4") (pinfunction "COL_4") (pintype "passive"))
      (node (ref "U7") (pin "22") (pinfunction "VDD_22") (pintype "bidirectional"))
      (node (ref "U7") (pin "25") (pinfunction "VBAT_25") (pintype "bidirectional"))
      (node (ref "U8") (pin "5") (pinfunction "5:GND_5") (pintype "bidirectional"))
    )
    (net (code "58") (name "5V") (class "Default")
      (node (ref "CN8") (pin "VCC") (pinfunction "VCC_VCC") (pintype "bidirectional"))
      (node (ref "I2C0") (pin "VCC") (pinfunction "VCC_VCC") (pintype "bidirectional"))
      (node (ref "LED1") (pin "VCC") (pinfunction "VCC_VCC") (pintype "bidirectional"))
      (node (ref "R47") (pin "2") (pinfunction "2_2") (pintype "bidirectional"))
      (node (ref "R53") (pin "2") (pinfunction "2_2") (pintype "bidirectional"))
      (node (ref "U$3") (pin "2") (pinfunction "5V_2") (pintype "bidirectional"))
    )
    (net (code "59") (name "BEC_62") (class "Default")
      (node (ref "D2") (pin "A") (pinfunction "ANODE_A") (pintype "bidirectional"))
      (node (ref "IN_1CH(ST)") (pin "VCC") (pinfunction "VCC_VCC") (pintype "bidirectional"))
      (node (ref "IN_2CH(TH)") (pin "VCC") (pinfunction "VCC_VCC") (pintype "bidirectional"))
      (node (ref "IN_3CH(SELECT)") (pin "VCC") (pinfunction "VCC_VCC") (pintype "bidirectional"))
      (node (ref "IN_CH4") (pin "VCC") (pinfunction "VCC_VCC") (pintype "bidirectional"))
      (node (ref "IN_CH5") (pin "VCC") (pinfunction "VCC_VCC") (pintype "bidirectional"))
      (node (ref "OUT_ST") (pin "VCC") (pinfunction "VCC_VCC") (pintype "bidirectional"))
      (node (ref "OUT_TH") (pin "VCC") (pinfunction "VCC_VCC") (pintype "bidirectional"))
      (node (ref "R15") (pin "2") (pinfunction "2_2") (pintype "bidirectional"))
      (node (ref "R16") (pin "2") (pinfunction "2_2") (pintype "bidirectional"))
      (node (ref "RCPWR") (pin "ANODE") (pinfunction "ANODE_ANODE") (pintype "passive"))
      (node (ref "U1") (pin "1") (pinfunction "A_1") (pintype "passive"))
      (node (ref "U5") (pin "1") (pinfunction "A_1") (pintype "passive"))
      (node (ref "U6") (pin "1") (pinfunction "A_1") (pintype "passive"))
    )
    (net (code "60") (name "GND") (class "Default")
      (node (ref "C1") (pin "2") (pinfunction "2_2") (pintype "passive"))
      (node (ref "C11") (pin "1") (pinfunction "1_1") (pintype "passive"))
      (node (ref "C12") (pin "1") (pinfunction "1_1") (pintype "passive"))
      (node (ref "C13") (pin "1") (pinfunction "1_1") (pintype "passive"))
      (node (ref "C16") (pin "1") (pinfunction "1_1") (pintype "passive"))
      (node (ref "C17") (pin "1") (pinfunction "1_1") (pintype "passive"))
      (node (ref "C18") (pin "1") (pinfunction "1_1") (pintype "passive"))
      (node (ref "C2") (pin "1") (pinfunction "1_1") (pintype "passive"))
      (node (ref "C23") (pin "1") (pinfunction "1_1") (pintype "passive"))
      (node (ref "C24") (pin "1") (pinfunction "1_1") (pintype "passive"))
      (node (ref "C25") (pin "1") (pinfunction "1_1") (pintype "passive"))
      (node (ref "C26") (pin "1") (pinfunction "1_1") (pintype "passive"))
      (node (ref "C27") (pin "1") (pinfunction "1_1") (pintype "passive"))
      (node (ref "C28") (pin "1") (pinfunction "1_1") (pintype "passive"))
      (node (ref "C3") (pin "2") (pinfunction "2_2") (pintype "passive"))
      (node (ref "C4") (pin "1") (pinfunction "1_1") (pintype "passive"))
      (node (ref "C5") (pin "1") (pinfunction "1_1") (pintype "passive"))
      (node (ref "C6") (pin "1") (pinfunction "1_1") (pintype "passive"))
      (node (ref "C7") (pin "1") (pinfunction "1_1") (pintype "passive"))
      (node (ref "C8") (pin "1") (pinfunction "1_1") (pintype "passive"))
      (node (ref "CN8") (pin "GND") (pinfunction "GND_GND") (pintype "bidirectional"))
      (node (ref "I2C0") (pin "GND") (pinfunction "GND_GND") (pintype "bidirectional"))
      (node (ref "IC1") (pin "2") (pinfunction "GND_2") (pintype "power_in"))
      (node (ref "IC4") (pin "1") (pinfunction "A0_1") (pintype "bidirectional"))
      (node (ref "IC4") (pin "14") (pinfunction "VSS_14") (pintype "bidirectional"))
      (node (ref "IC4") (pin "2") (pinfunction "A1_2") (pintype "bidirectional"))
      (node (ref "IC4") (pin "24") (pinfunction "A5_24") (pintype "bidirectional"))
      (node (ref "IC4") (pin "3") (pinfunction "A2_3") (pintype "bidirectional"))
      (node (ref "IC4") (pin "4") (pinfunction "A3_4") (pintype "bidirectional"))
      (node (ref "IC4") (pin "5") (pinfunction "A4_5") (pintype "bidirectional"))
      (node (ref "IC6") (pin "11") (pinfunction "FSYNC_11") (pintype "bidirectional"))
      (node (ref "IC6") (pin "18") (pinfunction "GND_18") (pintype "bidirectional"))
      (node (ref "IC6") (pin "20") (pinfunction "RESV_20") (pintype "bidirectional"))
      (node (ref "IN_1CH(ST)") (pin "GND") (pinfunction "GND_GND") (pintype "bidirectional"))
      (node (ref "IN_2CH(TH)") (pin "GND") (pinfunction "GND_GND") (pintype "bidirectional"))
      (node (ref "IN_3CH(SELECT)") (pin "GND") (pinfunction "GND_GND") (pintype "bidirectional"))
      (node (ref "IN_CH4") (pin "GND") (pinfunction "GND_GND") (pintype "bidirectional"))
      (node (ref "IN_CH5") (pin "GND") (pinfunction "GND_GND") (pintype "bidirectional"))
      (node (ref "LED1") (pin "GND") (pinfunction "GND_GND") (pintype "bidirectional"))
      (node (ref "OUT_ST") (pin "GND") (pinfunction "GND_GND") (pintype "bidirectional"))
      (node (ref "OUT_TH") (pin "GND") (pinfunction "GND_GND") (pintype "bidirectional"))
      (node (ref "Q1") (pin "S") (pinfunction "S_S") (pintype "passive"))
      (node (ref "Q10") (pin "S") (pinfunction "S_S") (pintype "passive"))
      (node (ref "Q2") (pin "S") (pinfunction "S_S") (pintype "passive"))
      (node (ref "Q3") (pin "S") (pinfunction "S_S") (pintype "passive"))
      (node (ref "Q4") (pin "S") (pinfunction "S_S") (pintype "passive"))
      (node (ref "Q5") (pin "S") (pinfunction "S_S") (pintype "passive"))
      (node (ref "Q7") (pin "S") (pinfunction "S_S") (pintype "passive"))
      (node (ref "R1") (pin "1") (pinfunction "1_1") (pintype "bidirectional"))
      (node (ref "R13") (pin "2") (pinfunction "2_2") (pintype "bidirectional"))
      (node (ref "R17") (pin "2") (pinfunction "2_2") (pintype "bidirectional"))
      (node (ref "R18") (pin "2") (pinfunction "2_2") (pintype "bidirectional"))
      (node (ref "R24") (pin "2") (pinfunction "2_2") (pintype "bidirectional"))
      (node (ref "R3") (pin "1") (pinfunction "1_1") (pintype "bidirectional"))
      (node (ref "R32") (pin "2") (pinfunction "2_2") (pintype "bidirectional"))
      (node (ref "R33") (pin "2") (pinfunction "2_2") (pintype "bidirectional"))
      (node (ref "R36") (pin "1") (pinfunction "1_1") (pintype "bidirectional"))
      (node (ref "R38") (pin "2") (pinfunction "2_2") (pintype "bidirectional"))
      (node (ref "R45") (pin "2") (pinfunction "2_2") (pintype "bidirectional"))
      (node (ref "R5") (pin "1") (pinfunction "1_1") (pintype "bidirectional"))
      (node (ref "R6") (pin "2") (pinfunction "2_2") (pintype "bidirectional"))
      (node (ref "R7") (pin "1") (pinfunction "1_1") (pintype "bidirectional"))
      (node (ref "R9") (pin "2") (pinfunction "2_2") (pintype "bidirectional"))
      (node (ref "SJ1") (pin "2") (pinfunction "2_2") (pintype "passive"))
      (node (ref "U$1") (pin "15") (pinfunction "15:E_15") (pintype "bidirectional"))
      (node (ref "U$1") (pin "8") (pinfunction "8:GND_8") (pintype "bidirectional"))
      (node (ref "U$10") (pin "1") (pinfunction "1:GND_1") (pintype "bidirectional"))
      (node (ref "U$11") (pin "#2") (pinfunction "2:CASE_GND_#2") (pintype "bidirectional"))
      (node (ref "U$3") (pin "14") (pinfunction "GND_14") (pintype "bidirectional"))
      (node (ref "U$3") (pin "20") (pinfunction "GND_20") (pintype "bidirectional"))
      (node (ref "U$3") (pin "25") (pinfunction "GND_25") (pintype "bidirectional"))
      (node (ref "U$3") (pin "30") (pinfunction "GND_30") (pintype "bidirectional"))
      (node (ref "U$3") (pin "34") (pinfunction "GND_34") (pintype "bidirectional"))
      (node (ref "U$3") (pin "39") (pinfunction "GND_39") (pintype "bidirectional"))
      (node (ref "U$3") (pin "9") (pinfunction "GND_9") (pintype "bidirectional"))
      (node (ref "U$8") (pin "3") (pinfunction "GND_3") (pintype "bidirectional"))
      (node (ref "U$9") (pin "1") (pinfunction "1:GND_1") (pintype "bidirectional"))
      (node (ref "U2") (pin "13") (pinfunction "GND_13") (pintype "bidirectional"))
      (node (ref "U4") (pin "13") (pinfunction "GND_13") (pintype "bidirectional"))
      (node (ref "U7") (pin "10") (pinfunction "D3_10") (pintype "bidirectional"))
      (node (ref "U7") (pin "14") (pinfunction "E/RD#_14") (pintype "bidirectional"))
      (node (ref "U7") (pin "15") (pinfunction "R/W#_15") (pintype "bidirectional"))
      (node (ref "U7") (pin "18") (pinfunction "CS#_18") (pintype "bidirectional"))
      (node (ref "U7") (pin "19") (pinfunction "BS2_19") (pintype "bidirectional"))
      (node (ref "U7") (pin "2") (pinfunction "VLSS_2") (pintype "bidirectional"))
      (node (ref "U7") (pin "21") (pinfunction "BS0_21") (pintype "bidirectional"))
      (node (ref "U7") (pin "23") (pinfunction "VSS_23") (pintype "bidirectional"))
      (node (ref "U7") (pin "6") (pinfunction "D7_6") (pintype "bidirectional"))
      (node (ref "U7") (pin "7") (pinfunction "D6_7") (pintype "bidirectional"))
      (node (ref "U7") (pin "8") (pinfunction "D5_8") (pintype "bidirectional"))
      (node (ref "U7") (pin "9") (pinfunction "D4_9") (pintype "bidirectional"))
      (node (ref "U8") (pin "8") (pinfunction "8:VDD__8") (pintype "bidirectional"))
    )
    (net (code "61") (name "Net-(C12-Pad2)") (class "Default")
      (node (ref "C12") (pin "2") (pinfunction "2_2") (pintype "passive"))
      (node (ref "D1") (pin "ANODE") (pinfunction "ANODE_ANODE") (pintype "bidirectional"))
      (node (ref "R25") (pin "2") (pinfunction "2_2") (pintype "bidirectional"))
      (node (ref "R31") (pin "1") (pinfunction "1_1") (pintype "bidirectional"))
    )
    (net (code "62") (name "Net-(CN8-PadCI)") (class "Default")
      (node (ref "CN8") (pin "CI") (pinfunction "CI_CI") (pintype "bidirectional"))
      (node (ref "LED1") (pin "CKO") (pinfunction "CKO_CKO") (pintype "bidirectional"))
    )
    (net (code "63") (name "Net-(CN8-PadDI)") (class "Default")
      (node (ref "CN8") (pin "DI") (pinfunction "DI_DI") (pintype "bidirectional"))
      (node (ref "LED1") (pin "SDO") (pinfunction "SDO_SDO") (pintype "bidirectional"))
    )
    (net (code "64") (name "Net-(D3-CATHODE)") (class "Default")
      (node (ref "D3") (pin "1") (pinfunction "CATHODE_1") (pintype "bidirectional"))
      (node (ref "U2") (pin "12") (pinfunction "3V3_12") (pintype "bidirectional"))
    )
    (net (code "65") (name "Net-(D4-CATHODE)") (class "Default")
      (node (ref "D4") (pin "1") (pinfunction "CATHODE_1") (pintype "bidirectional"))
      (node (ref "U4") (pin "12") (pinfunction "3V3_12") (pintype "bidirectional"))
    )
    (net (code "66") (name "Net-(IC1-BYPASS)") (class "Default")
      (node (ref "C6") (pin "2") (pinfunction "2_2") (pintype "passive"))
      (node (ref "IC1") (pin "4") (pinfunction "BYPASS_4") (pintype "bidirectional"))
    )
    (net (code "67") (name "Net-(IC1-VOUT)") (class "Default")
      (node (ref "C8") (pin "2") (pinfunction "2_2") (pintype "passive"))
      (node (ref "IC1") (pin "5") (pinfunction "VOUT_5") (pintype "output"))
      (node (ref "SJ4") (pin "1") (pinfunction "1_1") (pintype "passive"))
    )
    (net (code "68") (name "Net-(IC4-EXTCLK)") (class "Default")
      (node (ref "C3") (pin "1") (pinfunction "1_1") (pintype "passive"))
      (node (ref "IC4") (pin "25") (pinfunction "EXTCLK_25") (pintype "bidirectional"))
      (node (ref "R1") (pin "2") (pinfunction "2_2") (pintype "bidirectional"))
      (node (ref "U$11") (pin "#3") (pinfunction "3:OUTPUT_#3") (pintype "bidirectional"))
    )
    (net (code "69") (name "Net-(IC4-OE)") (class "Default")
      (node (ref "IC4") (pin "23") (pinfunction "OE_23") (pintype "bidirectional"))
      (node (ref "R3") (pin "2") (pinfunction "2_2") (pintype "bidirectional"))
    )
    (net (code "70") (name "Net-(IC6-INT)") (class "Default")
      (node (ref "IC6") (pin "12") (pinfunction "INT_12") (pintype "bidirectional"))
      (node (ref "INT") (pin "1") (pinfunction "1_1") (pintype "bidirectional"))
    )
    (net (code "71") (name "Net-(IC6-NCS)") (class "Default")
      (node (ref "IC6") (pin "22") (pinfunction "NCS_22") (pintype "bidirectional"))
      (node (ref "R57") (pin "1") (pinfunction "1_1") (pintype "bidirectional"))
      (node (ref "R58") (pin "1") (pinfunction "1_1") (pintype "bidirectional"))
    )
    (net (code "72") (name "Net-(IC6-REGOUT)") (class "Default")
      (node (ref "C28") (pin "2") (pinfunction "2_2") (pintype "passive"))
      (node (ref "IC6") (pin "10") (pinfunction "REGOUT_10") (pintype "bidirectional"))
    )
    (net (code "73") (name "Net-(LED9-Pad1)") (class "Default")
      (node (ref "LED9") (pin "1") (pinfunction "1_1") (pintype "bidirectional"))
      (node (ref "R53") (pin "1") (pinfunction "1_1") (pintype "bidirectional"))
    )
    (net (code "74") (name "Net-(LED9-Pad2)") (class "Default")
      (node (ref "LED9") (pin "2") (pinfunction "2_2") (pintype "bidirectional"))
      (node (ref "Q10") (pin "D") (pinfunction "D_D") (pintype "passive"))
    )
    (net (code "75") (name "Net-(LED10-Pad1)") (class "Default")
      (node (ref "LED10") (pin "1") (pinfunction "1_1") (pintype "bidirectional"))
      (node (ref "R47") (pin "1") (pinfunction "1_1") (pintype "bidirectional"))
    )
    (net (code "76") (name "Net-(LED10-Pad2)") (class "Default")
      (node (ref "LED10") (pin "2") (pinfunction "2_2") (pintype "bidirectional"))
      (node (ref "Q7") (pin "D") (pinfunction "D_D") (pintype "passive"))
    )
    (net (code "77") (name "Net-(OUT_ST-PadI{slash}O)") (class "Default")
      (node (ref "OUT_ST") (pin "I/O") (pinfunction "I/O_I/O") (pintype "bidirectional"))
      (node (ref "R20") (pin "2") (pinfunction "2_2") (pintype "bidirectional"))
    )
    (net (code "78") (name "Net-(OUT_TH-PadI{slash}O)") (class "Default")
      (node (ref "OUT_TH") (pin "I/O") (pinfunction "I/O_I/O") (pintype "bidirectional"))
      (node (ref "R21") (pin "2") (pinfunction "2_2") (pintype "bidirectional"))
    )
    (net (code "79") (name "Net-(Q1-PadD)") (class "Default")
      (node (ref "Q1") (pin "D") (pinfunction "D_D") (pintype "passive"))
      (node (ref "R10") (pin "2") (pinfunction "2_2") (pintype "bidirectional"))
    )
    (net (code "80") (name "Net-(Q1-PadG)") (class "Default")
      (node (ref "Q1") (pin "G") (pinfunction "G_G") (pintype "passive"))
      (node (ref "R18") (pin "1") (pinfunction "1_1") (pintype "bidirectional"))
      (node (ref "R30") (pin "2") (pinfunction "2_2") (pintype "bidirectional"))
    )
    (net (code "81") (name "Net-(Q2-PadD)") (class "Default")
      (node (ref "Q2") (pin "D") (pinfunction "D_D") (pintype "passive"))
      (node (ref "R14") (pin "2") (pinfunction "2_2") (pintype "bidirectional"))
    )
    (net (code "82") (name "Net-(Q2-PadG)") (class "Default")
      (node (ref "Q2") (pin "G") (pinfunction "G_G") (pintype "passive"))
      (node (ref "R17") (pin "1") (pinfunction "1_1") (pintype "bidirectional"))
      (node (ref "R28") (pin "2") (pinfunction "2_2") (pintype "bidirectional"))
    )
    (net (code "83") (name "Net-(Q3-PadD)") (class "Default")
      (node (ref "Q3") (pin "D") (pinfunction "D_D") (pintype "passive"))
      (node (ref "R26") (pin "2") (pinfunction "2_2") (pintype "bidirectional"))
    )
    (net (code "84") (name "Net-(Q3-PadG)") (class "Default")
      (node (ref "Q3") (pin "G") (pinfunction "G_G") (pintype "passive"))
      (node (ref "R24") (pin "1") (pinfunction "1_1") (pintype "bidirectional"))
      (node (ref "R8") (pin "1") (pinfunction "1_1") (pintype "bidirectional"))
    )
    (net (code "85") (name "Net-(Q4-PadD)") (class "Default")
      (node (ref "Q4") (pin "D") (pinfunction "D_D") (pintype "passive"))
      (node (ref "R27") (pin "2") (pinfunction "2_2") (pintype "bidirectional"))
    )
    (net (code "86") (name "Net-(Q4-PadG)") (class "Default")
      (node (ref "Q4") (pin "G") (pinfunction "G_G") (pintype "passive"))
      (node (ref "R33") (pin "1") (pinfunction "1_1") (pintype "bidirectional"))
      (node (ref "R35") (pin "2") (pinfunction "2_2") (pintype "bidirectional"))
    )
    (net (code "87") (name "Net-(Q5-PadD)") (class "Default")
      (node (ref "Q5") (pin "D") (pinfunction "D_D") (pintype "passive"))
      (node (ref "R29") (pin "2") (pinfunction "2_2") (pintype "bidirectional"))
    )
    (net (code "88") (name "Net-(Q5-PadG)") (class "Default")
      (node (ref "Q5") (pin "G") (pinfunction "G_G") (pintype "passive"))
      (node (ref "R32") (pin "1") (pinfunction "1_1") (pintype "bidirectional"))
      (node (ref "R34") (pin "2") (pinfunction "2_2") (pintype "bidirectional"))
    )
    (net (code "89") (name "Net-(Q7-PadG)") (class "Default")
      (node (ref "Q7") (pin "G") (pinfunction "G_G") (pintype "passive"))
      (node (ref "R48") (pin "1") (pinfunction "1_1") (pintype "bidirectional"))
    )
    (net (code "90") (name "Net-(Q10-PadG)") (class "Default")
      (node (ref "Q10") (pin "G") (pinfunction "G_G") (pintype "passive"))
      (node (ref "R54") (pin "1") (pinfunction "1_1") (pintype "bidirectional"))
    )
    (net (code "91") (name "Net-(Q12-PadG)") (class "Default")
      (node (ref "Q12") (pin "G") (pinfunction "G_G") (pintype "passive"))
      (node (ref "R65") (pin "1") (pinfunction "1_1") (pintype "bidirectional"))
    )
    (net (code "92") (name "Net-(Q13-PadG)") (class "Default")
      (node (ref "Q13") (pin "G") (pinfunction "G_G") (pintype "passive"))
      (node (ref "R67") (pin "1") (pinfunction "1_1") (pintype "bidirectional"))
    )
    (net (code "93") (name "Net-(R7-Pad2)") (class "Default")
      (node (ref "R7") (pin "2") (pinfunction "2_2") (pintype "bidirectional"))
      (node (ref "RCPWR") (pin "CATHODE") (pinfunction "CATHODE_CATHODE") (pintype "passive"))
    )
    (net (code "94") (name "Net-(U$1-1:S)") (class "Default")
      (node (ref "R5") (pin "2") (pinfunction "2_2") (pintype "bidirectional"))
      (node (ref "R63") (pin "2") (pinfunction "2_2") (pintype "bidirectional"))
      (node (ref "U$1") (pin "1") (pinfunction "1:S_1") (pintype "bidirectional"))
    )
    (net (code "95") (name "Net-(U$8-OE)") (class "Default")
      (node (ref "R45") (pin "1") (pinfunction "1_1") (pintype "bidirectional"))
      (node (ref "U$8") (pin "1") (pinfunction "OE_1") (pintype "bidirectional"))
    )
    (net (code "96") (name "Net-(U$8-Y)") (class "Default")
      (node (ref "R63") (pin "1") (pinfunction "1_1") (pintype "bidirectional"))
      (node (ref "R64") (pin "2") (pinfunction "2_2") (pintype "bidirectional"))
      (node (ref "U$8") (pin "4") (pinfunction "Y_4") (pintype "bidirectional"))
    )
    (net (code "97") (name "Net-(U$9-2:SENSOR1)") (class "Default")
      (node (ref "R39") (pin "1") (pinfunction "1_1") (pintype "bidirectional"))
      (node (ref "R42") (pin "2") (pinfunction "2_2") (pintype "bidirectional"))
      (node (ref "U$9") (pin "2") (pinfunction "2:SENSOR1_2") (pintype "bidirectional"))
    )
    (net (code "98") (name "Net-(U$9-3:SENSOR2)") (class "Default")
      (node (ref "R40") (pin "1") (pinfunction "1_1") (pintype "bidirectional"))
      (node (ref "R43") (pin "2") (pinfunction "2_2") (pintype "bidirectional"))
      (node (ref "U$9") (pin "3") (pinfunction "3:SENSOR2_3") (pintype "bidirectional"))
    )
    (net (code "99") (name "Net-(U$9-4:SENSOR3)") (class "Default")
      (node (ref "R41") (pin "1") (pinfunction "1_1") (pintype "bidirectional"))
      (node (ref "R44") (pin "2") (pinfunction "2_2") (pintype "bidirectional"))
      (node (ref "U$9") (pin "4") (pinfunction "4:SENSOR3_4") (pintype "bidirectional"))
    )
    (net (code "100") (name "Net-(U$10-2:SENSOR1)") (class "Default")
      (node (ref "R42") (pin "1") (pinfunction "1_1") (pintype "bidirectional"))
      (node (ref "U$10") (pin "2") (pinfunction "2:SENSOR1_2") (pintype "bidirectional"))
    )
    (net (code "101") (name "Net-(U$10-3:SENSOR2)") (class "Default")
      (node (ref "R43") (pin "1") (pinfunction "1_1") (pintype "bidirectional"))
      (node (ref "U$10") (pin "3") (pinfunction "3:SENSOR2_3") (pintype "bidirectional"))
    )
    (net (code "102") (name "Net-(U$10-4:SENSOR3)") (class "Default")
      (node (ref "R44") (pin "1") (pinfunction "1_1") (pintype "bidirectional"))
      (node (ref "U$10") (pin "4") (pinfunction "4:SENSOR3_4") (pintype "bidirectional"))
    )
    (net (code "103") (name "Net-(U$10-5:NC)") (class "Default")
      (node (ref "U$10") (pin "5") (pinfunction "5:NC_5") (pintype "bidirectional"))
      (node (ref "U$9") (pin "5") (pinfunction "5:NC_5") (pintype "bidirectional"))
    )
    (net (code "104") (name "Net-(U$10-6:VCC)") (class "Default")
      (node (ref "U$10") (pin "6") (pinfunction "6:VCC_6") (pintype "bidirectional"))
      (node (ref "U$9") (pin "6") (pinfunction "6:VCC_6") (pintype "bidirectional"))
    )
    (net (code "105") (name "Net-(U1-C)") (class "Default")
      (node (ref "R26") (pin "1") (pinfunction "1_1") (pintype "bidirectional"))
      (node (ref "U1") (pin "2") (pinfunction "C_2") (pintype "passive"))
    )
    (net (code "106") (name "Net-(U2-PA02_A0_D0)") (class "Default")
      (node (ref "R39") (pin "2") (pinfunction "2_2") (pintype "bidirectional"))
      (node (ref "U2") (pin "1") (pinfunction "PA02_A0_D0_1") (pintype "bidirectional"))
    )
    (net (code "107") (name "Net-(U2-PA4_A1_D1)") (class "Default")
      (node (ref "R40") (pin "2") (pinfunction "2_2") (pintype "bidirectional"))
      (node (ref "U2") (pin "2") (pinfunction "PA4_A1_D1_2") (pintype "bidirectional"))
    )
    (net (code "108") (name "Net-(U2-PA5_A9_D9_MISO)") (class "Default")
      (node (ref "MISO") (pin "1") (pinfunction "1_1") (pintype "bidirectional"))
      (node (ref "U2") (pin "10") (pinfunction "PA5_A9_D9_MISO_10") (pintype "bidirectional"))
    )
    (net (code "109") (name "Net-(U2-PA6_A10_D10_MOSI)") (class "Default")
      (node (ref "MOSI") (pin "1") (pinfunction "1_1") (pintype "bidirectional"))
      (node (ref "U2") (pin "11") (pinfunction "PA6_A10_D10_MOSI_11") (pintype "bidirectional"))
    )
    (net (code "110") (name "Net-(U2-PA7_A8_D8_SCK)") (class "Default")
      (node (ref "SCLK") (pin "1") (pinfunction "1_1") (pintype "bidirectional"))
      (node (ref "U2") (pin "9") (pinfunction "PA7_A8_D8_SCK_9") (pintype "bidirectional"))
    )
    (net (code "111") (name "Net-(U2-PA10_A2_D2)") (class "Default")
      (node (ref "R41") (pin "2") (pinfunction "2_2") (pintype "bidirectional"))
      (node (ref "U2") (pin "3") (pinfunction "PA10_A2_D2_3") (pintype "bidirectional"))
    )
    (net (code "112") (name "Net-(U2-PB08_D6_TX)") (class "Default")
      (node (ref "INT1") (pin "1") (pinfunction "1_1") (pintype "bidirectional"))
      (node (ref "U2") (pin "7") (pinfunction "PB08_D6_TX_7") (pintype "bidirectional"))
    )
    (net (code "113") (name "Net-(U2-PB09_D7_RX)") (class "Default")
      (node (ref "INT2") (pin "1") (pinfunction "1_1") (pintype "bidirectional"))
      (node (ref "U2") (pin "8") (pinfunction "PB09_D7_RX_8") (pintype "bidirectional"))
    )
    (net (code "114") (name "Net-(U5-C)") (class "Default")
      (node (ref "R14") (pin "1") (pinfunction "1_1") (pintype "bidirectional"))
      (node (ref "U5") (pin "2") (pinfunction "C_2") (pintype "passive"))
    )
    (net (code "115") (name "Net-(U6-C)") (class "Default")
      (node (ref "R10") (pin "1") (pinfunction "1_1") (pintype "bidirectional"))
      (node (ref "U6") (pin "2") (pinfunction "C_2") (pintype "passive"))
    )
    (net (code "116") (name "Net-(U7-BS1)") (class "Default")
      (node (ref "R19") (pin "2") (pinfunction "2_2") (pintype "bidirectional"))
      (node (ref "U7") (pin "20") (pinfunction "BS1_20") (pintype "bidirectional"))
    )
    (net (code "117") (name "Net-(U7-C1N)") (class "Default")
      (node (ref "C19") (pin "1") (pinfunction "1_1") (pintype "passive"))
      (node (ref "U7") (pin "26") (pinfunction "C1N_26") (pintype "bidirectional"))
    )
    (net (code "118") (name "Net-(U7-C1P)") (class "Default")
      (node (ref "C19") (pin "2") (pinfunction "2_2") (pintype "passive"))
      (node (ref "U7") (pin "27") (pinfunction "C1P_27") (pintype "bidirectional"))
    )
    (net (code "119") (name "Net-(U7-C2N)") (class "Default")
      (node (ref "C22") (pin "1") (pinfunction "1_1") (pintype "passive"))
      (node (ref "U7") (pin "28") (pinfunction "C2N_28") (pintype "bidirectional"))
    )
    (net (code "120") (name "Net-(U7-C2P)") (class "Default")
      (node (ref "C22") (pin "2") (pinfunction "2_2") (pintype "passive"))
      (node (ref "U7") (pin "29") (pinfunction "C2P_29") (pintype "bidirectional"))
    )
    (net (code "121") (name "Net-(U7-D{slash}C#)") (class "Default")
      (node (ref "R36") (pin "2") (pinfunction "2_2") (pintype "bidirectional"))
      (node (ref "R37") (pin "1") (pinfunction "1_1") (pintype "bidirectional"))
      (node (ref "U7") (pin "16") (pinfunction "D/C#_16") (pintype "bidirectional"))
    )
    (net (code "122") (name "Net-(U7-IREF)") (class "Default")
      (node (ref "R13") (pin "1") (pinfunction "1_1") (pintype "bidirectional"))
      (node (ref "U7") (pin "5") (pinfunction "IREF_5") (pintype "bidirectional"))
    )
    (net (code "123") (name "Net-(U7-RES#)") (class "Default")
      (node (ref "R31") (pin "2") (pinfunction "2_2") (pintype "bidirectional"))
      (node (ref "U7") (pin "17") (pinfunction "RES#_17") (pintype "bidirectional"))
    )
    (net (code "124") (name "Net-(U7-VCC)") (class "Default")
      (node (ref "C13") (pin "2") (pinfunction "2_2") (pintype "passive"))
      (node (ref "U7") (pin "3") (pinfunction "VCC_3") (pintype "bidirectional"))
    )
    (net (code "125") (name "Net-(U7-VCOMH)") (class "Default")
      (node (ref "C16") (pin "2") (pinfunction "2_2") (pintype "passive"))
      (node (ref "U7") (pin "4") (pinfunction "VCOMH_4") (pintype "bidirectional"))
    )
    (net (code "126") (name "Net-(U8-1:AN1)") (class "Default")
      (node (ref "R15") (pin "1") (pinfunction "1_1") (pintype "bidirectional"))
      (node (ref "U8") (pin "1") (pinfunction "1:AN1_1") (pintype "bidirectional"))
    )
    (net (code "127") (name "Net-(U8-2:CA1)") (class "Default")
      (node (ref "R27") (pin "1") (pinfunction "1_1") (pintype "bidirectional"))
      (node (ref "U8") (pin "2") (pinfunction "2:CA1_2") (pintype "bidirectional"))
    )
    (net (code "128") (name "Net-(U8-3:CA2)") (class "Default")
      (node (ref "R29") (pin "1") (pinfunction "1_1") (pintype "bidirectional"))
      (node (ref "U8") (pin "3") (pinfunction "3:CA2_3") (pintype "bidirectional"))
    )
    (net (code "129") (name "Net-(U8-4:AN2)") (class "Default")
      (node (ref "R16") (pin "1") (pinfunction "1_1") (pintype "bidirectional"))
      (node (ref "U8") (pin "4") (pinfunction "4:AN2_4") (pintype "bidirectional"))
    )
    (net (code "130") (name "XIAO_5V") (class "Default")
      (node (ref "U4") (pin "14") (pinfunction "5V_14") (pintype "bidirectional"))
    )
    (net (code "131") (name "XIAO_SEC_5V") (class "Default")
      (node (ref "U2") (pin "14") (pinfunction "5V_14") (pintype "bidirectional"))
    )
    (net (code "132") (name "unconnected-(IC4-LED2-Pad8)") (class "Default")
      (node (ref "IC4") (pin "8") (pinfunction "LED2_8") (pintype "bidirectional"))
    )
    (net (code "133") (name "unconnected-(IC4-LED3-Pad9)") (class "Default")
      (node (ref "IC4") (pin "9") (pinfunction "LED3_9") (pintype "bidirectional"))
    )
    (net (code "134") (name "unconnected-(IC4-LED4-Pad10)") (class "Default")
      (node (ref "IC4") (pin "10") (pinfunction "LED4_10") (pintype "bidirectional"))
    )
    (net (code "135") (name "unconnected-(IC4-LED5-Pad11)") (class "Default")
      (node (ref "IC4") (pin "11") (pinfunction "LED5_11") (pintype "bidirectional"))
    )
    (net (code "136") (name "unconnected-(IC4-LED6-Pad12)") (class "Default")
      (node (ref "IC4") (pin "12") (pinfunction "LED6_12") (pintype "bidirectional"))
    )
    (net (code "137") (name "unconnected-(IC4-LED7-Pad13)") (class "Default")
      (node (ref "IC4") (pin "13") (pinfunction "LED7_13") (pintype "bidirectional"))
    )
    (net (code "138") (name "unconnected-(IC4-LED8-Pad15)") (class "Default")
      (node (ref "IC4") (pin "15") (pinfunction "LED8_15") (pintype "bidirectional"))
    )
    (net (code "139") (name "unconnected-(IC4-LED11-Pad18)") (class "Default")
      (node (ref "IC4") (pin "18") (pinfunction "LED11_18") (pintype "bidirectional"))
    )
    (net (code "140") (name "unconnected-(IC4-LED12-Pad19)") (class "Default")
      (node (ref "IC4") (pin "19") (pinfunction "LED12_19") (pintype "bidirectional"))
    )
    (net (code "141") (name "unconnected-(IC4-LED13-Pad20)") (class "Default")
      (node (ref "IC4") (pin "20") (pinfunction "LED13_20") (pintype "bidirectional"))
    )
    (net (code "142") (name "unconnected-(IC4-LED14-Pad21)") (class "Default")
      (node (ref "IC4") (pin "21") (pinfunction "LED14_21") (pintype "bidirectional"))
    )
    (net (code "143") (name "unconnected-(IC4-LED15-Pad22)") (class "Default")
      (node (ref "IC4") (pin "22") (pinfunction "LED15_22") (pintype "bidirectional"))
    )
    (net (code "144") (name "unconnected-(IC6-AUX_CL-Pad7)") (class "Default")
      (node (ref "IC6") (pin "7") (pinfunction "AUX_CL_7") (pintype "bidirectional"))
    )
    (net (code "145") (name "unconnected-(IC6-AUX_DA-Pad21)") (class "Default")
      (node (ref "IC6") (pin "21") (pinfunction "AUX_DA_21") (pintype "bidirectional"))
    )
    (net (code "146") (name "unconnected-(IC6-NC-Pad2)") (class "Default")
      (node (ref "IC6") (pin "2") (pinfunction "NC_2") (pintype "bidirectional"))
    )
    (net (code "147") (name "unconnected-(IC6-NC-Pad3)") (class "Default")
      (node (ref "IC6") (pin "3") (pinfunction "NC_3") (pintype "bidirectional"))
    )
    (net (code "148") (name "unconnected-(IC6-NC-Pad4)") (class "Default")
      (node (ref "IC6") (pin "4") (pinfunction "NC_4") (pintype "bidirectional"))
    )
    (net (code "149") (name "unconnected-(IC6-NC-Pad5)") (class "Default")
      (node (ref "IC6") (pin "5") (pinfunction "NC_5") (pintype "bidirectional"))
    )
    (net (code "150") (name "unconnected-(IC6-NC-Pad6)") (class "Default")
      (node (ref "IC6") (pin "6") (pinfunction "NC_6") (pintype "bidirectional"))
    )
    (net (code "151") (name "unconnected-(IC6-NC-Pad14)") (class "Default")
      (node (ref "IC6") (pin "14") (pinfunction "NC_14") (pintype "bidirectional"))
    )
    (net (code "152") (name "unconnected-(IC6-NC-Pad15)") (class "Default")
      (node (ref "IC6") (pin "15") (pinfunction "NC_15") (pintype "bidirectional"))
    )
    (net (code "153") (name "unconnected-(IC6-NC-Pad16)") (class "Default")
      (node (ref "IC6") (pin "16") (pinfunction "NC_16") (pintype "bidirectional"))
    )
    (net (code "154") (name "unconnected-(IC6-NC-Pad17)") (class "Default")
      (node (ref "IC6") (pin "17") (pinfunction "NC_17") (pintype "bidirectional"))
    )
    (net (code "155") (name "unconnected-(IC6-RESV-Pad19)") (class "Default")
      (node (ref "IC6") (pin "19") (pinfunction "RESV_19") (pintype "bidirectional"))
    )
    (net (code "156") (name "unconnected-(U$1-9:Y2-Pad9)") (class "Default")
      (node (ref "U$1") (pin "9") (pinfunction "9:Y2_9") (pintype "bidirectional"))
    )
    (net (code "157") (name "unconnected-(U$1-10:B2-Pad10)") (class "Default")
      (node (ref "U$1") (pin "10") (pinfunction "10:B2_10") (pintype "bidirectional"))
    )
    (net (code "158") (name "unconnected-(U$1-11:A2-Pad11)") (class "Default")
      (node (ref "U$1") (pin "11") (pinfunction "11:A2_11") (pintype "bidirectional"))
    )
    (net (code "159") (name "unconnected-(U$1-12:Y3-Pad12)") (class "Default")
      (node (ref "U$1") (pin "12") (pinfunction "12:Y3_12") (pintype "bidirectional"))
    )
    (net (code "160") (name "unconnected-(U$1-13:B3-Pad13)") (class "Default")
      (node (ref "U$1") (pin "13") (pinfunction "13:B3_13") (pintype "bidirectional"))
    )
    (net (code "161") (name "unconnected-(U$1-14:A3-Pad14)") (class "Default")
      (node (ref "U$1") (pin "14") (pinfunction "14:A3_14") (pintype "bidirectional"))
    )
    (net (code "162") (name "unconnected-(U$3-CE1-Pad26)") (class "Default")
      (node (ref "U$3") (pin "26") (pinfunction "CE1_26") (pintype "bidirectional"))
    )
    (net (code "163") (name "unconnected-(U$3-ID_SC-Pad27)") (class "Default")
      (node (ref "U$3") (pin "27") (pinfunction "ID_SC_27") (pintype "bidirectional"))
    )
    (net (code "164") (name "unconnected-(U$3-ID_SD-Pad28)") (class "Default")
      (node (ref "U$3") (pin "28") (pinfunction "ID_SD_28") (pintype "bidirectional"))
    )
    (net (code "165") (name "unconnected-(U2-PA11_A3_D3-Pad4)") (class "Default")
      (node (ref "U2") (pin "4") (pinfunction "PA11_A3_D3_4") (pintype "bidirectional"))
    )
    (net (code "166") (name "unconnected-(U4-PA5_A9_D9_MISO-Pad10)") (class "Default")
      (node (ref "U4") (pin "10") (pinfunction "PA5_A9_D9_MISO_10") (pintype "bidirectional"))
    )
    (net (code "167") (name "unconnected-(U7-NC-Pad1)") (class "Default")
      (node (ref "U7") (pin "1") (pinfunction "NC_1") (pintype "bidirectional"))
    )
    (net (code "168") (name "unconnected-(U7-NC-Pad24)") (class "Default")
      (node (ref "U7") (pin "24") (pinfunction "NC_24") (pintype "bidirectional"))
    )
    (net (code "169") (name "unconnected-(U7-NC-Pad30)") (class "Default")
      (node (ref "U7") (pin "30") (pinfunction "NC_30") (pintype "bidirectional"))
    )
  )
)
